# HTMD-PREAMP2.net
KiCad netlist of a schematic drawn in Altium Designer
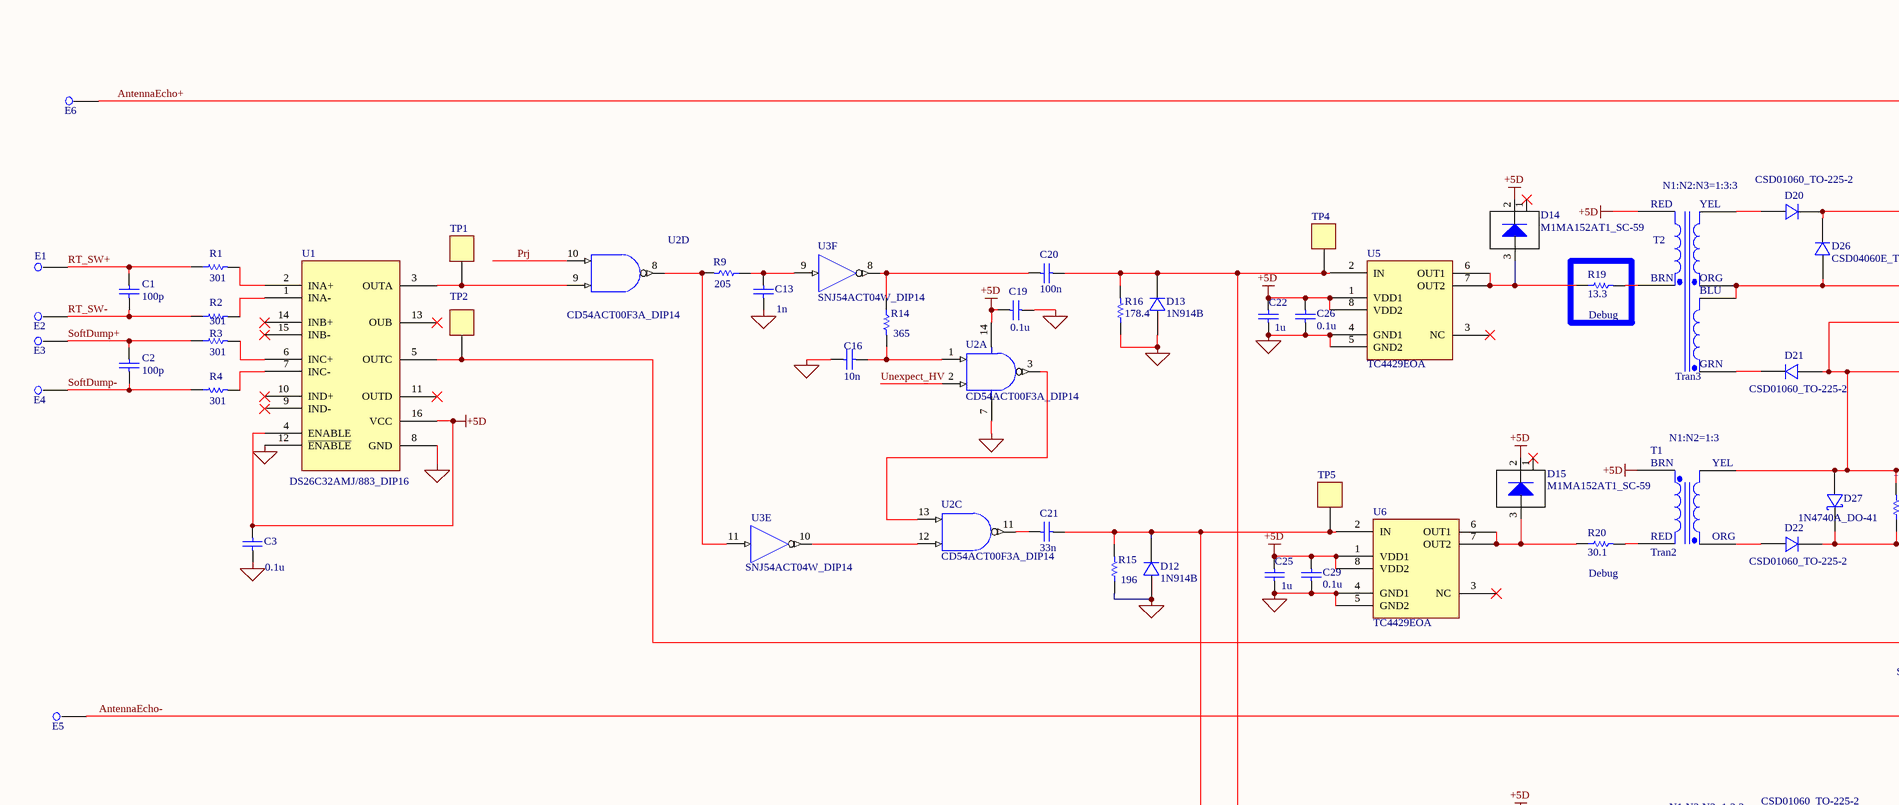
[diagram p0: HTMD-PREAMP2.SCHDOC, top left]
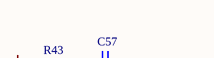
[diagram p1: HTMD-PREAMP2.SCHDOC, top right]
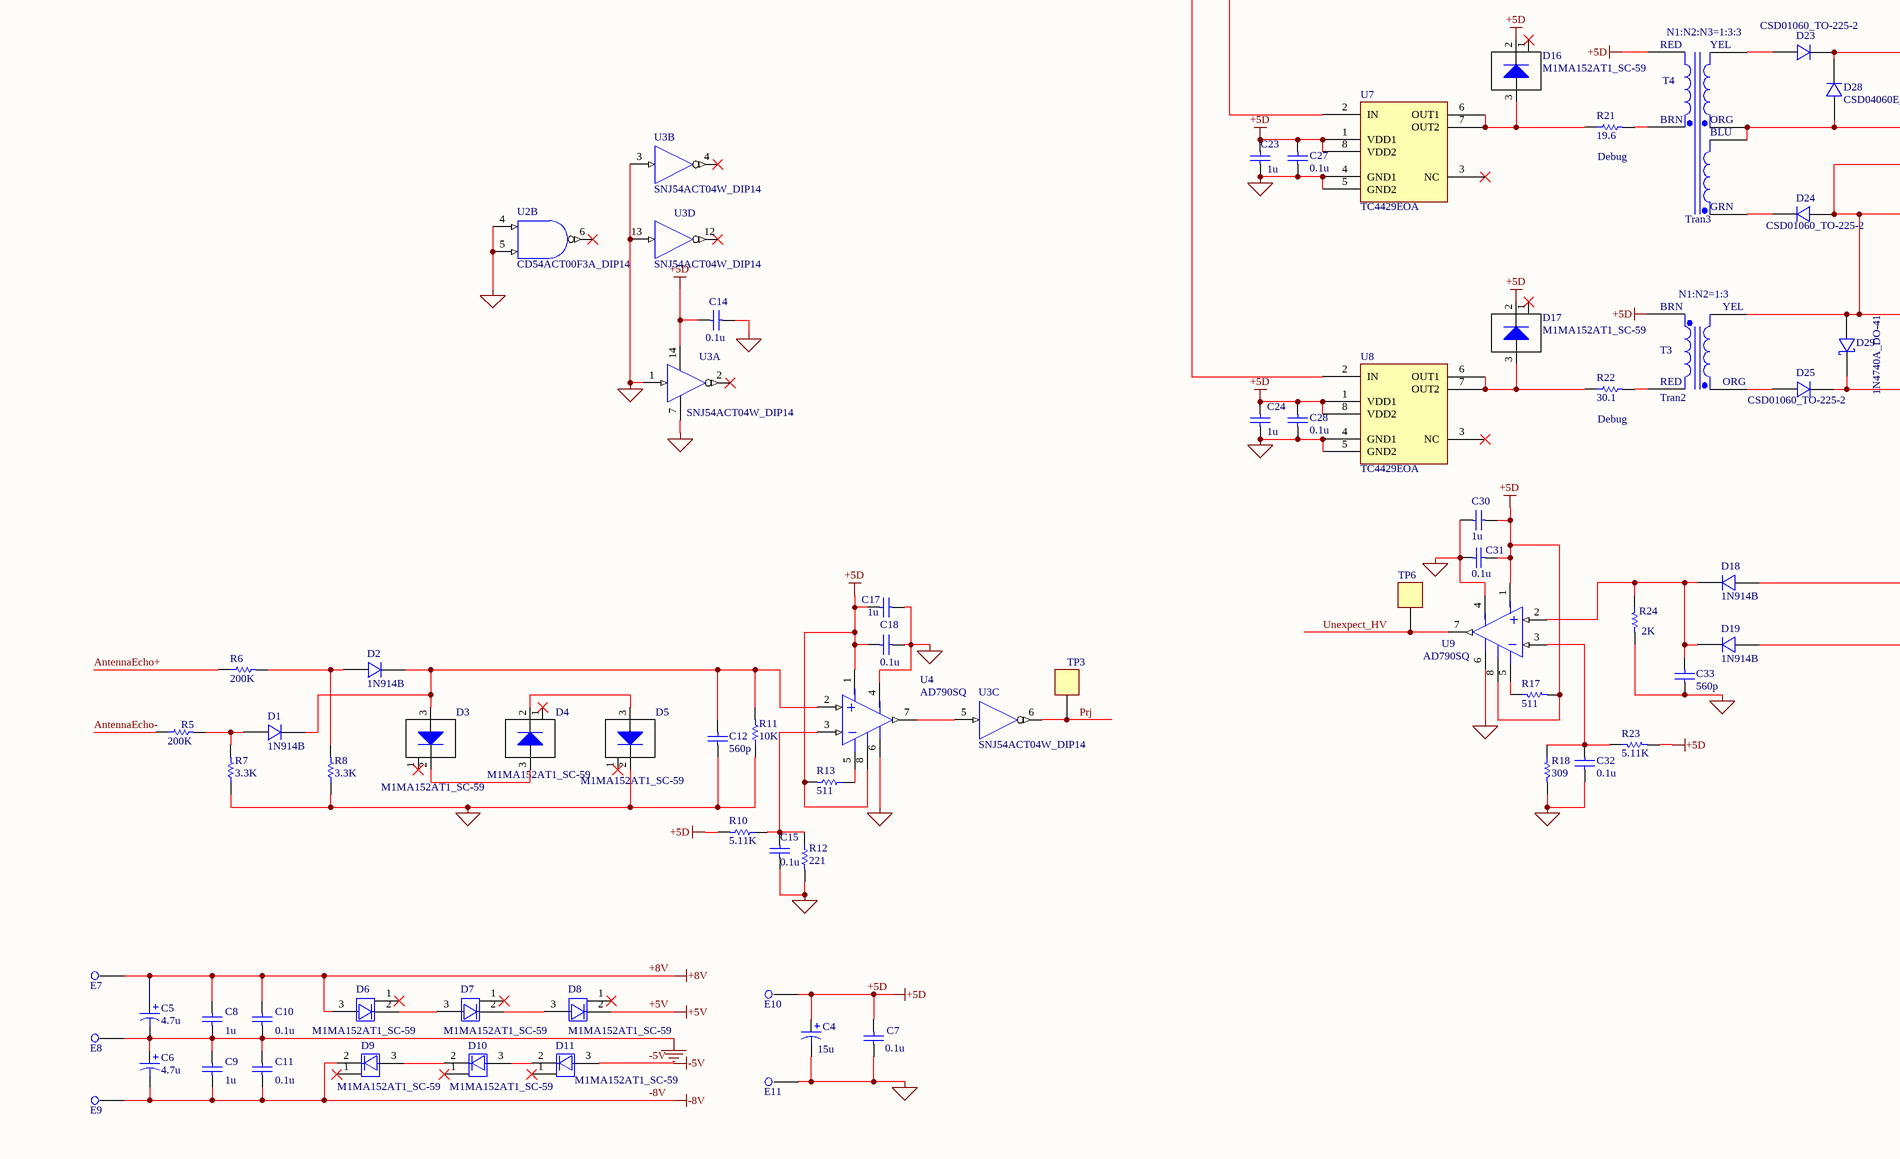
[diagram p2: HTMD-PREAMP2.SCHDOC, bottom left]
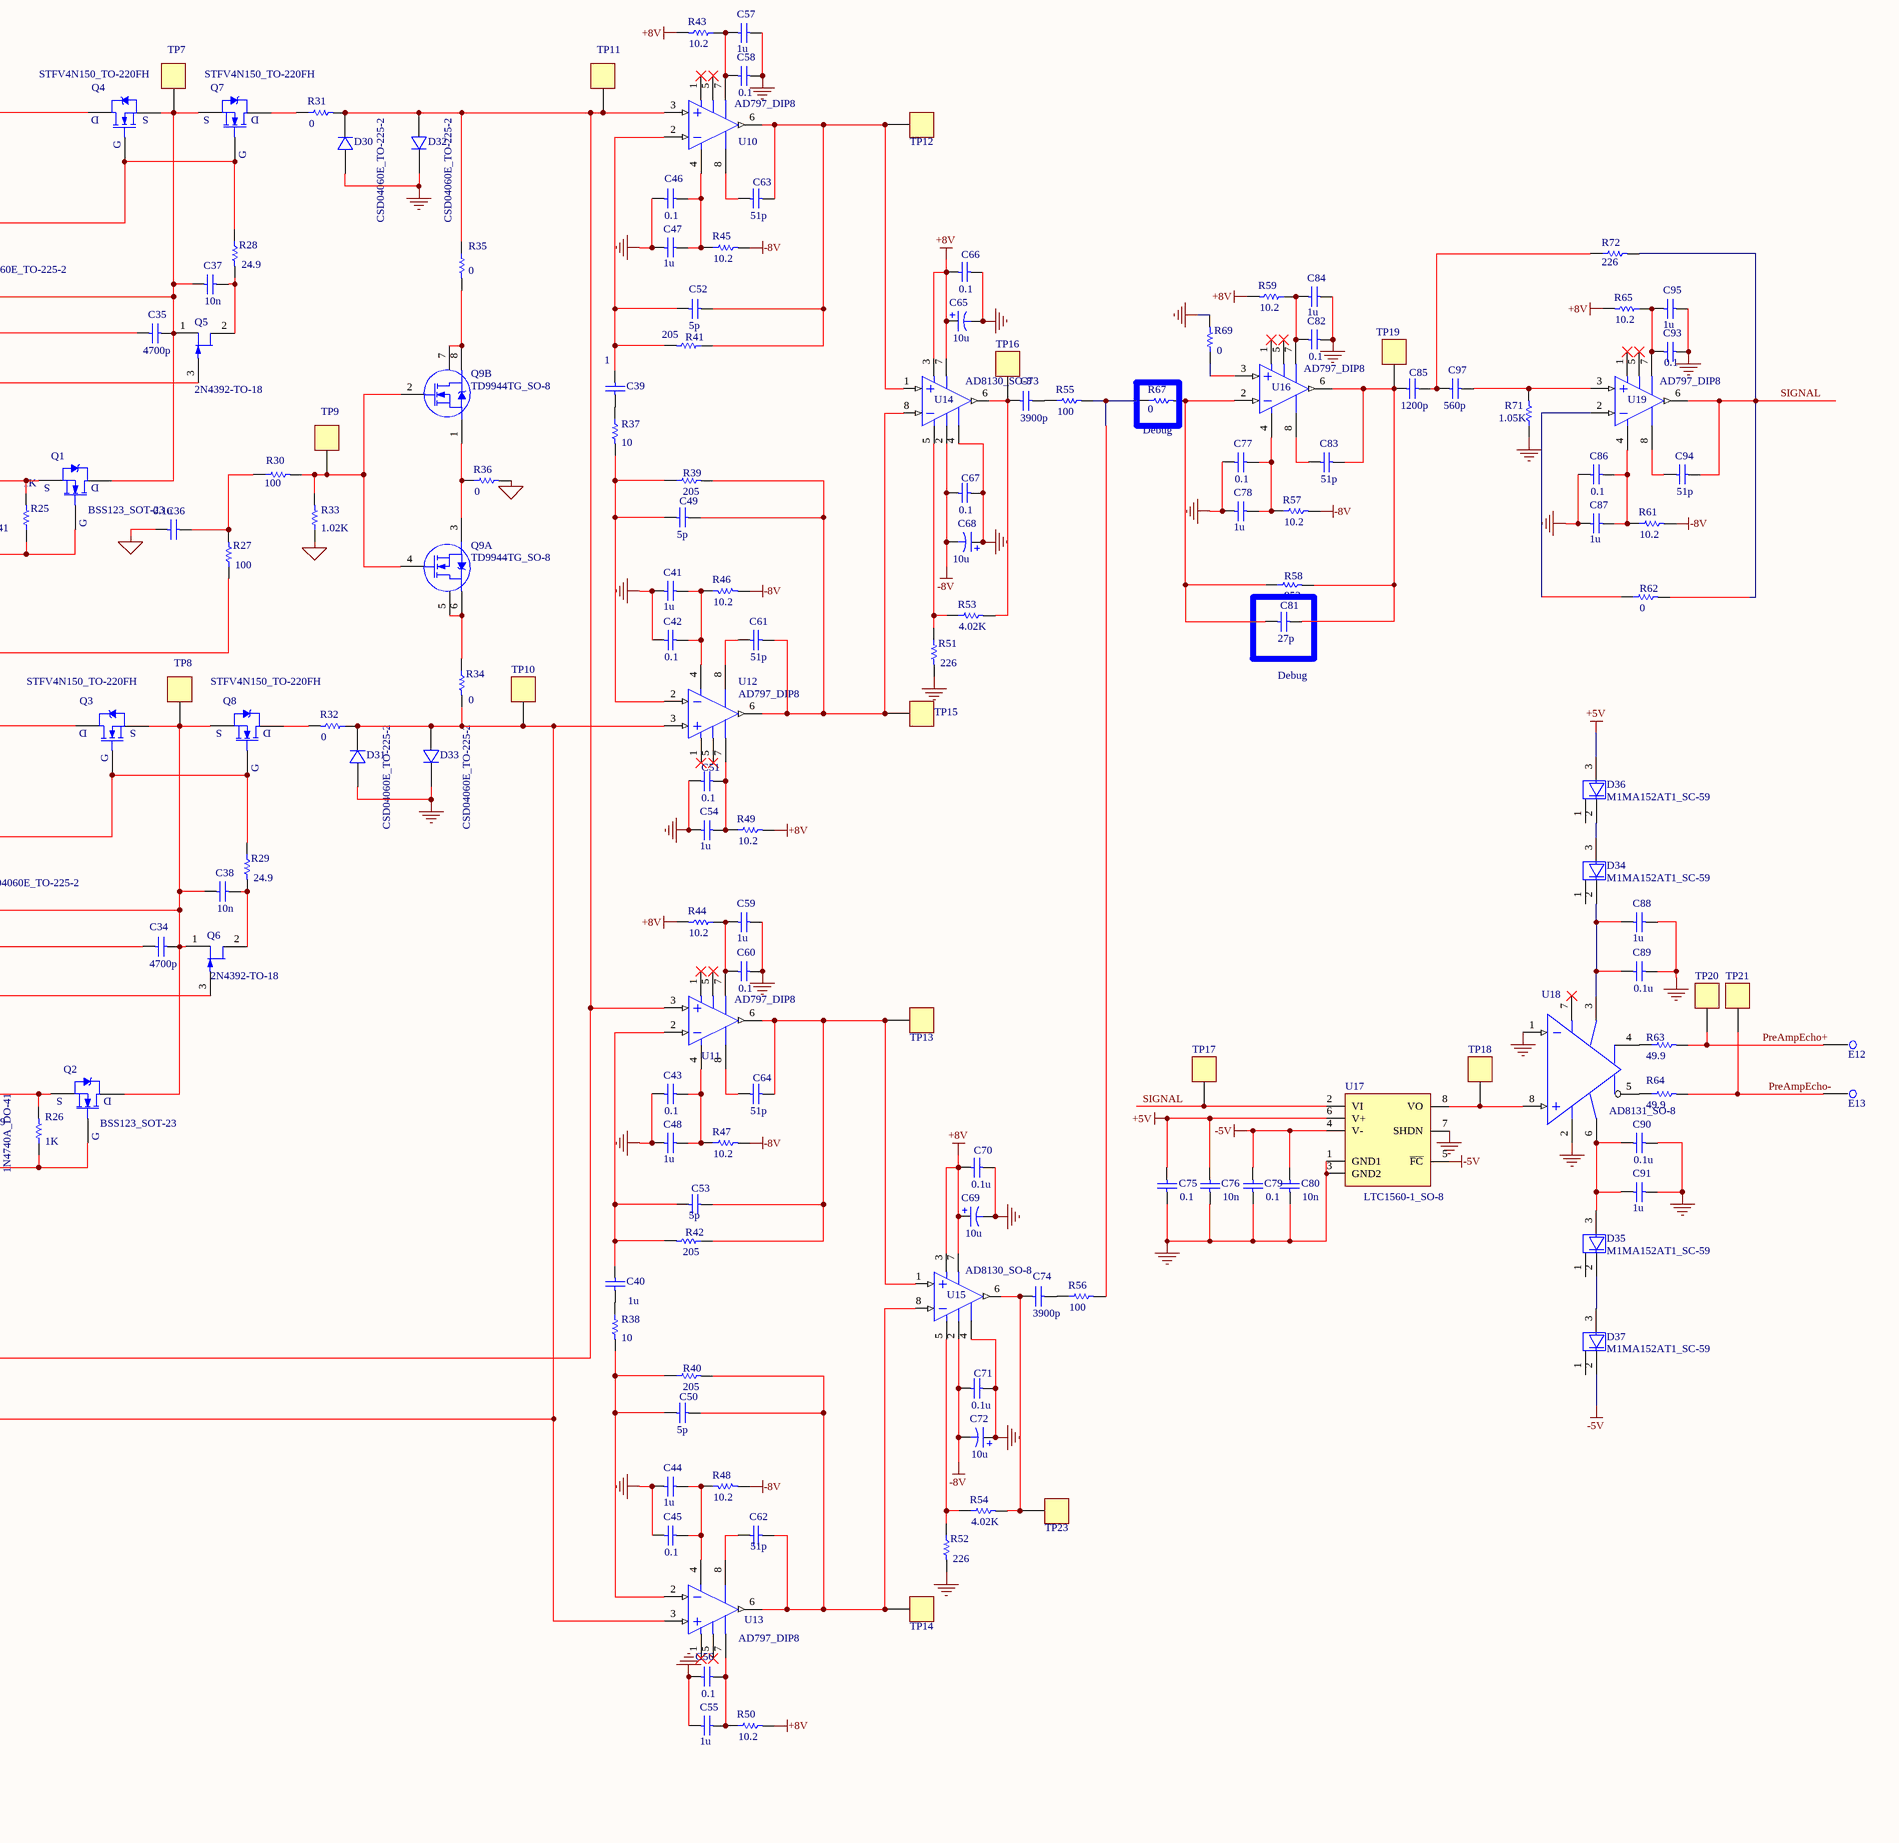
[diagram p3: HTMD-PREAMP2.SCHDOC, bottom right]

(export (version "E")
  (design (tool "Eeschema 10.0.6"))
  (components
    (comp (ref "C1")
      (value "100p")
      (footprint "C0805")
      (description "Capacitor")
      (fields (field (name "PUBLISHER") "Altium Limited"))
      (libsource (lib "*") (part "Cap"))
    )
    (comp (ref "C2")
      (value "100p")
      (footprint "C0805")
      (description "Capacitor")
      (fields (field (name "PUBLISHER") "Altium Limited"))
      (libsource (lib "*") (part "Cap"))
    )
    (comp (ref "C3")
      (value "0.1u")
      (footprint "C0805")
      (description "Capacitor")
      (fields (field (name "PUBLISHER") "Altium Limited"))
      (libsource (lib "*") (part "Cap"))
    )
    (comp (ref "C4")
      (value "15u")
      (footprint "7343")
      (description "Polarized Capacitor (Radial)")
      (fields (field (name "PUBLISHER") "Altium Limited"))
      (libsource (lib "*") (part "Cap Pol1"))
    )
    (comp (ref "C5")
      (value "4.7u")
      (footprint "7343")
      (description "Polarized Capacitor (Radial)")
      (fields (field (name "PUBLISHER") "Altium Limited"))
      (libsource (lib "*") (part "Cap Pol1"))
    )
    (comp (ref "C6")
      (value "4.7u")
      (footprint "7343")
      (description "Polarized Capacitor (Radial)")
      (fields (field (name "PUBLISHER") "Altium Limited"))
      (libsource (lib "*") (part "Cap Pol1"))
    )
    (comp (ref "C7")
      (value "0.1u")
      (footprint "C0805")
      (description "Capacitor")
      (fields (field (name "PUBLISHER") "Altium Limited"))
      (libsource (lib "*") (part "Cap"))
    )
    (comp (ref "C8")
      (value "1u")
      (footprint "C1206")
      (description "Capacitor")
      (fields (field (name "PUBLISHER") "Altium Limited"))
      (libsource (lib "*") (part "Cap"))
    )
    (comp (ref "C9")
      (value "1u")
      (footprint "C1206")
      (description "Capacitor")
      (fields (field (name "PUBLISHER") "Altium Limited"))
      (libsource (lib "*") (part "Cap"))
    )
    (comp (ref "C10")
      (value "0.1u")
      (footprint "C0805")
      (description "Capacitor")
      (fields (field (name "PUBLISHER") "Altium Limited"))
      (libsource (lib "*") (part "Cap"))
    )
    (comp (ref "C11")
      (value "0.1u")
      (footprint "C0805")
      (description "Capacitor")
      (fields (field (name "PUBLISHER") "Altium Limited"))
      (libsource (lib "*") (part "Cap"))
    )
    (comp (ref "C12")
      (value "560p")
      (footprint "C0805")
      (description "Capacitor")
      (fields (field (name "PUBLISHER") "Altium Limited"))
      (libsource (lib "Miscellaneous Devices") (part "Cap"))
    )
    (comp (ref "C13")
      (value "1n")
      (footprint "1206")
      (description "Capacitor")
      (fields (field (name "PUBLISHER") "Altium Limited"))
      (libsource (lib "*") (part "Cap"))
    )
    (comp (ref "C14")
      (value "0.1u")
      (footprint "C0805")
      (description "Capacitor")
      (fields (field (name "PUBLISHER") "Altium Limited"))
      (libsource (lib "*") (part "Cap"))
    )
    (comp (ref "C15")
      (value "0.1u")
      (footprint "C0805")
      (description "Capacitor")
      (fields (field (name "PUBLISHER") "Altium Limited"))
      (libsource (lib "*") (part "Cap"))
    )
    (comp (ref "C16")
      (value "10n")
      (footprint "C0805")
      (description "Capacitor")
      (fields (field (name "PUBLISHER") "Altium Limited"))
      (libsource (lib "*") (part "Cap"))
    )
    (comp (ref "C17")
      (value "1u")
      (footprint "C1206")
      (description "Capacitor")
      (fields (field (name "PUBLISHER") "Altium Limited"))
      (libsource (lib "*") (part "Cap"))
    )
    (comp (ref "C18")
      (value "0.1u")
      (footprint "C0805")
      (description "Capacitor")
      (fields (field (name "PUBLISHER") "Altium Limited"))
      (libsource (lib "*") (part "Cap"))
    )
    (comp (ref "C19")
      (value "0.1u")
      (footprint "C0805")
      (description "Capacitor")
      (fields (field (name "PUBLISHER") "Altium Limited"))
      (libsource (lib "*") (part "Cap"))
    )
    (comp (ref "C20")
      (value "100n")
      (footprint "C0805")
      (description "Capacitor")
      (fields (field (name "PUBLISHER") "Altium Limited"))
      (libsource (lib "*") (part "Cap"))
    )
    (comp (ref "C21")
      (value "33n")
      (footprint "1206")
      (description "Capacitor")
      (fields (field (name "PUBLISHER") "Altium Limited"))
      (libsource (lib "*") (part "Cap"))
    )
    (comp (ref "C22")
      (value "1u")
      (footprint "C1206")
      (description "Capacitor")
      (fields (field (name "PUBLISHER") "Altium Limited"))
      (libsource (lib "*") (part "Cap"))
    )
    (comp (ref "C23")
      (value "1u")
      (footprint "C1206")
      (description "Capacitor")
      (fields (field (name "PUBLISHER") "Altium Limited"))
      (libsource (lib "*") (part "Cap"))
    )
    (comp (ref "C24")
      (value "1u")
      (footprint "C1206")
      (description "Capacitor")
      (fields (field (name "PUBLISHER") "Altium Limited"))
      (libsource (lib "*") (part "Cap"))
    )
    (comp (ref "C25")
      (value "1u")
      (footprint "C1206")
      (description "Capacitor")
      (fields (field (name "PUBLISHER") "Altium Limited"))
      (libsource (lib "*") (part "Cap"))
    )
    (comp (ref "C26")
      (value "0.1u")
      (footprint "C0805")
      (description "Capacitor")
      (fields (field (name "PUBLISHER") "Altium Limited"))
      (libsource (lib "*") (part "Cap"))
    )
    (comp (ref "C27")
      (value "0.1u")
      (footprint "C0805")
      (description "Capacitor")
      (fields (field (name "PUBLISHER") "Altium Limited"))
      (libsource (lib "*") (part "Cap"))
    )
    (comp (ref "C28")
      (value "0.1u")
      (footprint "C0805")
      (description "Capacitor")
      (fields (field (name "PUBLISHER") "Altium Limited"))
      (libsource (lib "*") (part "Cap"))
    )
    (comp (ref "C29")
      (value "0.1u")
      (footprint "C0805")
      (description "Capacitor")
      (fields (field (name "PUBLISHER") "Altium Limited"))
      (libsource (lib "*") (part "Cap"))
    )
    (comp (ref "C30")
      (value "1u")
      (footprint "C1206")
      (description "Capacitor")
      (fields (field (name "PUBLISHER") "Altium Limited"))
      (libsource (lib "*") (part "Cap"))
    )
    (comp (ref "C31")
      (value "0.1u")
      (footprint "C0805")
      (description "Capacitor")
      (fields (field (name "PUBLISHER") "Altium Limited"))
      (libsource (lib "*") (part "Cap"))
    )
    (comp (ref "C32")
      (value "0.1u")
      (footprint "C0805")
      (description "Capacitor")
      (fields (field (name "PUBLISHER") "Altium Limited"))
      (libsource (lib "*") (part "Cap"))
    )
    (comp (ref "C33")
      (value "560p")
      (footprint "C0805")
      (description "Capacitor")
      (fields (field (name "PUBLISHER") "Altium Limited"))
      (libsource (lib "*") (part "Cap"))
    )
    (comp (ref "C34")
      (value "4700p")
      (footprint "C0805")
      (description "Capacitor")
      (fields (field (name "PUBLISHER") "Altium Limited"))
      (libsource (lib "*") (part "Cap"))
    )
    (comp (ref "C35")
      (value "4700p")
      (footprint "C0805")
      (description "Capacitor")
      (fields (field (name "PUBLISHER") "Altium Limited"))
      (libsource (lib "*") (part "Cap"))
    )
    (comp (ref "C36")
      (value "0.1u")
      (footprint "C0805")
      (description "Capacitor")
      (fields (field (name "PUBLISHER") "Altium Limited"))
      (libsource (lib "*") (part "Cap"))
    )
    (comp (ref "C37")
      (value "10n")
      (footprint "1206")
      (description "Capacitor")
      (fields (field (name "PUBLISHER") "Altium Limited"))
      (libsource (lib "*") (part "Cap"))
    )
    (comp (ref "C38")
      (value "10n")
      (footprint "1206")
      (description "Capacitor")
      (fields (field (name "PUBLISHER") "Altium Limited"))
      (libsource (lib "*") (part "Cap"))
    )
    (comp (ref "C39")
      (value "1")
      (footprint "1206")
      (description "Capacitor")
      (fields (field (name "PUBLISHER") "Altium Limited"))
      (libsource (lib "*") (part "Cap"))
    )
    (comp (ref "C40")
      (value "1u")
      (footprint "1206")
      (description "Capacitor")
      (fields (field (name "PUBLISHER") "Altium Limited"))
      (libsource (lib "*") (part "Cap"))
    )
    (comp (ref "C41")
      (value "1u")
      (footprint "C1206")
      (description "Capacitor")
      (fields (field (name "PUBLISHER") "Altium Limited"))
      (libsource (lib "*") (part "Cap"))
    )
    (comp (ref "C42")
      (value "0.1")
      (footprint "C0805")
      (description "Capacitor")
      (fields (field (name "PUBLISHER") "Altium Limited"))
      (libsource (lib "*") (part "Cap"))
    )
    (comp (ref "C43")
      (value "0.1")
      (footprint "C0805")
      (description "Capacitor")
      (fields (field (name "PUBLISHER") "Altium Limited"))
      (libsource (lib "*") (part "Cap"))
    )
    (comp (ref "C44")
      (value "1u")
      (footprint "C1206")
      (description "Capacitor")
      (fields (field (name "PUBLISHER") "Altium Limited"))
      (libsource (lib "*") (part "Cap"))
    )
    (comp (ref "C45")
      (value "0.1")
      (footprint "C0805")
      (description "Capacitor")
      (fields (field (name "PUBLISHER") "Altium Limited"))
      (libsource (lib "*") (part "Cap"))
    )
    (comp (ref "C46")
      (value "0.1")
      (footprint "C0805")
      (description "Capacitor")
      (fields (field (name "PUBLISHER") "Altium Limited"))
      (libsource (lib "*") (part "Cap"))
    )
    (comp (ref "C47")
      (value "1u")
      (footprint "C1206")
      (description "Capacitor")
      (fields (field (name "PUBLISHER") "Altium Limited"))
      (libsource (lib "*") (part "Cap"))
    )
    (comp (ref "C48")
      (value "1u")
      (footprint "C1206")
      (description "Capacitor")
      (fields (field (name "PUBLISHER") "Altium Limited"))
      (libsource (lib "*") (part "Cap"))
    )
    (comp (ref "C49")
      (value "5p")
      (footprint "C0805")
      (description "Capacitor")
      (fields (field (name "PUBLISHER") "Altium Limited"))
      (libsource (lib "*") (part "Cap"))
    )
    (comp (ref "C50")
      (value "5p")
      (footprint "C0805")
      (description "Capacitor")
      (fields (field (name "PUBLISHER") "Altium Limited"))
      (libsource (lib "*") (part "Cap"))
    )
    (comp (ref "C51")
      (value "0.1")
      (footprint "C0805")
      (description "Capacitor")
      (fields (field (name "PUBLISHER") "Altium Limited"))
      (libsource (lib "*") (part "Cap"))
    )
    (comp (ref "C52")
      (value "5p")
      (footprint "C0805")
      (description "Capacitor")
      (fields (field (name "PUBLISHER") "Altium Limited"))
      (libsource (lib "*") (part "Cap"))
    )
    (comp (ref "C53")
      (value "5p")
      (footprint "C0805")
      (description "Capacitor")
      (fields (field (name "PUBLISHER") "Altium Limited"))
      (libsource (lib "*") (part "Cap"))
    )
    (comp (ref "C54")
      (value "1u")
      (footprint "C1206")
      (description "Capacitor")
      (fields (field (name "PUBLISHER") "Altium Limited"))
      (libsource (lib "*") (part "Cap"))
    )
    (comp (ref "C55")
      (value "1u")
      (footprint "C1206")
      (description "Capacitor")
      (fields (field (name "PUBLISHER") "Altium Limited"))
      (libsource (lib "*") (part "Cap"))
    )
    (comp (ref "C56")
      (value "0.1")
      (footprint "C0805")
      (description "Capacitor")
      (fields (field (name "PUBLISHER") "Altium Limited"))
      (libsource (lib "*") (part "Cap"))
    )
    (comp (ref "C57")
      (value "1u")
      (footprint "C1206")
      (description "Capacitor")
      (fields (field (name "PUBLISHER") "Altium Limited"))
      (libsource (lib "*") (part "Cap"))
    )
    (comp (ref "C58")
      (value "0.1")
      (footprint "C0805")
      (description "Capacitor")
      (fields (field (name "PUBLISHER") "Altium Limited"))
      (libsource (lib "*") (part "Cap"))
    )
    (comp (ref "C59")
      (value "1u")
      (footprint "C1206")
      (description "Capacitor")
      (fields (field (name "PUBLISHER") "Altium Limited"))
      (libsource (lib "*") (part "Cap"))
    )
    (comp (ref "C60")
      (value "0.1")
      (footprint "C0805")
      (description "Capacitor")
      (fields (field (name "PUBLISHER") "Altium Limited"))
      (libsource (lib "*") (part "Cap"))
    )
    (comp (ref "C61")
      (value "51p")
      (footprint "C0805")
      (description "Capacitor")
      (fields (field (name "PUBLISHER") "Altium Limited"))
      (libsource (lib "*") (part "Cap"))
    )
    (comp (ref "C62")
      (value "51p")
      (footprint "C0805")
      (description "Capacitor")
      (fields (field (name "PUBLISHER") "Altium Limited"))
      (libsource (lib "*") (part "Cap"))
    )
    (comp (ref "C63")
      (value "51p")
      (footprint "C0805")
      (description "Capacitor")
      (fields (field (name "PUBLISHER") "Altium Limited"))
      (libsource (lib "*") (part "Cap"))
    )
    (comp (ref "C64")
      (value "51p")
      (footprint "C0805")
      (description "Capacitor")
      (fields (field (name "PUBLISHER") "Altium Limited"))
      (libsource (lib "*") (part "Cap"))
    )
    (comp (ref "C65")
      (value "10u")
      (footprint "7343")
      (description "Polarized Capacitor (Surface Mount)")
      (fields (field (name "PUBLISHER") "Altium Limited"))
      (libsource (lib "Miscellaneous Devices") (part "Cap Pol3"))
    )
    (comp (ref "C66")
      (value "0.1")
      (footprint "C0805")
      (description "Capacitor")
      (fields (field (name "PUBLISHER") "Altium Limited"))
      (libsource (lib "*") (part "Cap"))
    )
    (comp (ref "C67")
      (value "0.1")
      (footprint "C0805")
      (description "Capacitor")
      (fields (field (name "PUBLISHER") "Altium Limited"))
      (libsource (lib "*") (part "Cap"))
    )
    (comp (ref "C68")
      (value "10u")
      (footprint "7343")
      (description "Polarized Capacitor (Surface Mount)")
      (fields (field (name "PUBLISHER") "Altium Limited"))
      (libsource (lib "Miscellaneous Devices") (part "Cap Pol3"))
    )
    (comp (ref "C69")
      (value "10u")
      (footprint "7343")
      (description "Polarized Capacitor (Surface Mount)")
      (fields (field (name "PUBLISHER") "Altium Limited"))
      (libsource (lib "Miscellaneous Devices") (part "Cap Pol3"))
    )
    (comp (ref "C70")
      (value "0.1u")
      (footprint "C0805")
      (description "Capacitor")
      (fields (field (name "PUBLISHER") "Altium Limited"))
      (libsource (lib "*") (part "Cap"))
    )
    (comp (ref "C71")
      (value "0.1u")
      (footprint "C0805")
      (description "Capacitor")
      (fields (field (name "PUBLISHER") "Altium Limited"))
      (libsource (lib "*") (part "Cap"))
    )
    (comp (ref "C72")
      (value "10u")
      (footprint "7343")
      (description "Polarized Capacitor (Surface Mount)")
      (fields (field (name "PUBLISHER") "Altium Limited"))
      (libsource (lib "Miscellaneous Devices") (part "Cap Pol3"))
    )
    (comp (ref "C73")
      (value "3900p")
      (footprint "1206")
      (description "Capacitor")
      (fields (field (name "PUBLISHER") "Altium Limited"))
      (libsource (lib "*") (part "Cap"))
    )
    (comp (ref "C74")
      (value "3900p")
      (footprint "1206")
      (description "Capacitor")
      (fields (field (name "PUBLISHER") "Altium Limited"))
      (libsource (lib "*") (part "Cap"))
    )
    (comp (ref "C75")
      (value "0.1")
      (footprint "C0805")
      (description "Capacitor")
      (fields (field (name "PUBLISHER") "Altium Limited"))
      (libsource (lib "*") (part "Cap"))
    )
    (comp (ref "C76")
      (value "10n")
      (footprint "C0805")
      (description "Capacitor")
      (fields (field (name "PUBLISHER") "Altium Limited"))
      (libsource (lib "*") (part "Cap"))
    )
    (comp (ref "C77")
      (value "0.1")
      (footprint "C0805")
      (description "Capacitor")
      (fields (field (name "PUBLISHER") "Altium Limited"))
      (libsource (lib "*") (part "Cap"))
    )
    (comp (ref "C78")
      (value "1u")
      (footprint "C1206")
      (description "Capacitor")
      (fields (field (name "PUBLISHER") "Altium Limited"))
      (libsource (lib "*") (part "Cap"))
    )
    (comp (ref "C79")
      (value "0.1")
      (footprint "C0805")
      (description "Capacitor")
      (fields (field (name "PUBLISHER") "Altium Limited"))
      (libsource (lib "*") (part "Cap"))
    )
    (comp (ref "C80")
      (value "10n")
      (footprint "C0805")
      (description "Capacitor")
      (fields (field (name "PUBLISHER") "Altium Limited"))
      (libsource (lib "*") (part "Cap"))
    )
    (comp (ref "C81")
      (value "27p")
      (footprint "C0805")
      (description "Capacitor")
      (fields (field (name "PUBLISHER") "Altium Limited"))
      (libsource (lib "*") (part "Cap"))
    )
    (comp (ref "C82")
      (value "0.1")
      (footprint "C0805")
      (description "Capacitor")
      (fields (field (name "PUBLISHER") "Altium Limited"))
      (libsource (lib "*") (part "Cap"))
    )
    (comp (ref "C83")
      (value "51p")
      (footprint "C0805")
      (description "Capacitor")
      (fields (field (name "PUBLISHER") "Altium Limited"))
      (libsource (lib "*") (part "Cap"))
    )
    (comp (ref "C84")
      (value "1u")
      (footprint "C1206")
      (description "Capacitor")
      (fields (field (name "PUBLISHER") "Altium Limited"))
      (libsource (lib "*") (part "Cap"))
    )
    (comp (ref "C85")
      (value "1200p")
      (footprint "C0805")
      (description "Capacitor")
      (fields (field (name "PUBLISHER") "Altium Limited"))
      (libsource (lib "*") (part "Cap"))
    )
    (comp (ref "C86")
      (value "0.1")
      (footprint "C0805")
      (description "Capacitor")
      (fields (field (name "PUBLISHER") "Altium Limited"))
      (libsource (lib "*") (part "Cap"))
    )
    (comp (ref "C87")
      (value "1u")
      (footprint "C1206")
      (description "Capacitor")
      (fields (field (name "PUBLISHER") "Altium Limited"))
      (libsource (lib "*") (part "Cap"))
    )
    (comp (ref "C88")
      (value "1u")
      (footprint "C1206")
      (description "Capacitor")
      (fields (field (name "PUBLISHER") "Altium Limited"))
      (libsource (lib "*") (part "Cap"))
    )
    (comp (ref "C89")
      (value "0.1u")
      (footprint "C0805")
      (description "Capacitor")
      (fields (field (name "PUBLISHER") "Altium Limited"))
      (libsource (lib "*") (part "Cap"))
    )
    (comp (ref "C90")
      (value "0.1u")
      (footprint "C0805")
      (description "Capacitor")
      (fields (field (name "PUBLISHER") "Altium Limited"))
      (libsource (lib "*") (part "Cap"))
    )
    (comp (ref "C91")
      (value "1u")
      (footprint "C1206")
      (description "Capacitor")
      (fields (field (name "PUBLISHER") "Altium Limited"))
      (libsource (lib "*") (part "Cap"))
    )
    (comp (ref "C93")
      (value "0.1")
      (footprint "C0805")
      (description "Capacitor")
      (fields (field (name "PUBLISHER") "Altium Limited"))
      (libsource (lib "*") (part "Cap"))
    )
    (comp (ref "C94")
      (value "51p")
      (footprint "C0805")
      (description "Capacitor")
      (fields (field (name "PUBLISHER") "Altium Limited"))
      (libsource (lib "*") (part "Cap"))
    )
    (comp (ref "C95")
      (value "1u")
      (footprint "C1206")
      (description "Capacitor")
      (fields (field (name "PUBLISHER") "Altium Limited"))
      (libsource (lib "*") (part "Cap"))
    )
    (comp (ref "C97")
      (value "560p")
      (footprint "C0805")
      (description "Capacitor")
      (fields (field (name "PUBLISHER") "Altium Limited"))
      (libsource (lib "Miscellaneous Devices") (part "Cap"))
    )
    (comp (ref "D1") (value "1N914B") (footprint "DO-35") (libsource (lib "*") (part "1N914B")))
    (comp (ref "D2") (value "1N914B") (footprint "DO-35") (libsource (lib "*") (part "1N914B")))
    (comp (ref "D3")
      (value "M1MA152AT1_SC-59")
      (footprint "SC-59")
      (description "single silicon switching diodes")
      (fields (field (name "PUBLISHER") "Altium Limited"))
      (libsource (lib "") (part "M1MA152AT1_1"))
    )
    (comp (ref "D4")
      (value "M1MA152AT1_SC-59")
      (footprint "SC-59")
      (description "single silicon switching diodes")
      (fields (field (name "PUBLISHER") "Altium Limited"))
      (libsource (lib "") (part "M1MA152AT1_1"))
    )
    (comp (ref "D5")
      (value "M1MA152AT1_SC-59")
      (footprint "SC-59")
      (description "single silicon switching diodes")
      (fields (field (name "PUBLISHER") "Altium Limited"))
      (libsource (lib "") (part "M1MA152AT1_1"))
    )
    (comp (ref "D6") (value "M1MA152AT1_SC-59") (footprint "SC-59") (libsource (lib "*") (part "M1MA152AT1")))
    (comp (ref "D7") (value "M1MA152AT1_SC-59") (footprint "SC-59") (libsource (lib "*") (part "M1MA152AT1")))
    (comp (ref "D8") (value "M1MA152AT1_SC-59") (footprint "SC-59") (libsource (lib "*") (part "M1MA152AT1")))
    (comp (ref "D9") (value "M1MA152AT1_SC-59") (footprint "SC-59") (libsource (lib "*") (part "M1MA152AT1")))
    (comp (ref "D10")
      (value "M1MA152AT1_SC-59")
      (footprint "SC-59")
      (libsource (lib "*") (part "M1MA152AT1"))
    )
    (comp (ref "D11")
      (value "M1MA152AT1_SC-59")
      (footprint "SC-59")
      (libsource (lib "*") (part "M1MA152AT1"))
    )
    (comp (ref "D12") (value "1N914B") (footprint "DO-35") (libsource (lib "*") (part "1N914B")))
    (comp (ref "D13") (value "1N914B") (footprint "DO-35") (libsource (lib "*") (part "1N914B")))
    (comp (ref "D14")
      (value "M1MA152AT1_SC-59")
      (footprint "SC-59")
      (description "single silicon switching diodes")
      (fields (field (name "PUBLISHER") "Altium Limited"))
      (libsource (lib "*") (part "M1MA152AT1_1"))
    )
    (comp (ref "D15")
      (value "M1MA152AT1_SC-59")
      (footprint "SC-59")
      (description "single silicon switching diodes")
      (fields (field (name "PUBLISHER") "Altium Limited"))
      (libsource (lib "*") (part "M1MA152AT1_1"))
    )
    (comp (ref "D16")
      (value "M1MA152AT1_SC-59")
      (footprint "SC-59")
      (description "single silicon switching diodes")
      (fields (field (name "PUBLISHER") "Altium Limited"))
      (libsource (lib "*") (part "M1MA152AT1_1"))
    )
    (comp (ref "D17")
      (value "M1MA152AT1_SC-59")
      (footprint "SC-59")
      (description "single silicon switching diodes")
      (fields (field (name "PUBLISHER") "Altium Limited"))
      (libsource (lib "*") (part "M1MA152AT1_1"))
    )
    (comp (ref "D18") (value "1N914B") (footprint "DO-35") (libsource (lib "*") (part "1N914B")))
    (comp (ref "D19") (value "1N914B") (footprint "DO-35") (libsource (lib "*") (part "1N914B")))
    (comp (ref "D20")
      (value "CSD01060_TO-225-2")
      (footprint "TO-225-2")
      (description "CSD01060")
      (libsource (lib "*") (part "CSD01060"))
    )
    (comp (ref "D21")
      (value "CSD01060_TO-225-2")
      (footprint "TO-225-2")
      (description "CSD01060")
      (libsource (lib "*") (part "CSD01060"))
    )
    (comp (ref "D22")
      (value "CSD01060_TO-225-2")
      (footprint "TO-225-2")
      (description "CSD01060")
      (libsource (lib "*") (part "CSD01060"))
    )
    (comp (ref "D23")
      (value "CSD01060_TO-225-2")
      (footprint "TO-225-2")
      (description "CSD01060")
      (libsource (lib "*") (part "CSD01060"))
    )
    (comp (ref "D24")
      (value "CSD01060_TO-225-2")
      (footprint "TO-225-2")
      (description "CSD01060")
      (libsource (lib "*") (part "CSD01060"))
    )
    (comp (ref "D25")
      (value "CSD01060_TO-225-2")
      (footprint "TO-225-2")
      (description "CSD01060")
      (libsource (lib "*") (part "CSD01060"))
    )
    (comp (ref "D26")
      (value "CSD04060E_TO-225-2")
      (footprint "TO-225-2")
      (description "CSD04060E")
      (libsource (lib "*") (part "CSD04060E"))
    )
    (comp (ref "D27")
      (value "1N4740A_DO-41")
      (footprint "DO-41")
      (description "Schottky Rectifier")
      (libsource (lib "*") (part "1N4740A"))
    )
    (comp (ref "D28")
      (value "CSD04060E_TO-225-2")
      (footprint "TO-225-2")
      (description "CSD04060E")
      (libsource (lib "*") (part "CSD04060E"))
    )
    (comp (ref "D29")
      (value "1N4740A_DO-41")
      (footprint "DO-41")
      (description "Schottky Rectifier")
      (libsource (lib "*") (part "1N4740A"))
    )
    (comp (ref "D30")
      (value "CSD04060E_TO-225-2")
      (footprint "TO-225-2")
      (description "CSD04060E")
      (libsource (lib "*") (part "CSD04060E"))
    )
    (comp (ref "D31")
      (value "CSD04060E_TO-225-2")
      (footprint "TO-225-2")
      (description "CSD04060E")
      (libsource (lib "*") (part "CSD04060E"))
    )
    (comp (ref "D32")
      (value "CSD04060E_TO-225-2")
      (footprint "TO-225-2")
      (description "CSD04060E")
      (libsource (lib "*") (part "CSD04060E"))
    )
    (comp (ref "D33")
      (value "CSD04060E_TO-225-2")
      (footprint "TO-225-2")
      (description "CSD04060E")
      (libsource (lib "*") (part "CSD04060E"))
    )
    (comp (ref "D34")
      (value "M1MA152AT1_SC-59")
      (footprint "SC-59")
      (libsource (lib "*") (part "M1MA152AT1"))
    )
    (comp (ref "D35")
      (value "M1MA152AT1_SC-59")
      (footprint "SC-59")
      (libsource (lib "*") (part "M1MA152AT1"))
    )
    (comp (ref "D36")
      (value "M1MA152AT1_SC-59")
      (footprint "SC-59")
      (libsource (lib "*") (part "M1MA152AT1"))
    )
    (comp (ref "D37")
      (value "M1MA152AT1_SC-59")
      (footprint "SC-59")
      (libsource (lib "*") (part "M1MA152AT1"))
    )
    (comp (ref "E1") (value "InOut") (footprint "TermSignal") (libsource (lib "PreAmp") (part "InOut")))
    (comp (ref "E2") (value "InOut") (footprint "TermSignal") (libsource (lib "*") (part "InOut")))
    (comp (ref "E3") (value "InOut") (footprint "TermSignal") (libsource (lib "*") (part "InOut")))
    (comp (ref "E4") (value "InOut") (footprint "TermSignal") (libsource (lib "*") (part "InOut")))
    (comp (ref "E5") (value "InOut") (footprint "TermSignal") (libsource (lib "*") (part "InOut")))
    (comp (ref "E6") (value "InOut") (footprint "TermSignal") (libsource (lib "*") (part "InOut")))
    (comp (ref "E7") (value "InOut") (footprint "TermPower") (libsource (lib "*") (part "InOut")))
    (comp (ref "E8") (value "InOut") (footprint "TermPower") (libsource (lib "*") (part "InOut")))
    (comp (ref "E9") (value "InOut") (footprint "TermPower") (libsource (lib "*") (part "InOut")))
    (comp (ref "E10") (value "InOut") (footprint "TermPower") (libsource (lib "*") (part "InOut")))
    (comp (ref "E11") (value "InOut") (footprint "TermPower") (libsource (lib "*") (part "InOut")))
    (comp (ref "E12") (value "InOut") (footprint "TermSignal") (libsource (lib "*") (part "InOut")))
    (comp (ref "E13") (value "InOut") (footprint "TermSignal") (libsource (lib "*") (part "InOut")))
    (comp (ref "Q1")
      (value "BSS123_SOT-23")
      (footprint "SOT-23")
      (description "BSS123")
      (libsource (lib "*") (part "BSS123"))
    )
    (comp (ref "Q2")
      (value "BSS123_SOT-23")
      (footprint "SOT-23")
      (description "BSS123")
      (libsource (lib "*") (part "BSS123"))
    )
    (comp (ref "Q3")
      (value "STFV4N150_TO-220FH")
      (footprint "TO-220FH")
      (libsource (lib "*") (part "STFV4N150"))
    )
    (comp (ref "Q4")
      (value "STFV4N150_TO-220FH")
      (footprint "TO-220FH")
      (libsource (lib "*") (part "STFV4N150"))
    )
    (comp (ref "Q5") (value "2N4392-TO-18") (footprint "TO-18") (libsource (lib "*") (part "MPF4392")))
    (comp (ref "Q6") (value "2N4392-TO-18") (footprint "TO-18") (libsource (lib "*") (part "MPF4392")))
    (comp (ref "Q7")
      (value "STFV4N150_TO-220FH")
      (footprint "TO-220FH")
      (libsource (lib "*") (part "STFV4N150"))
    )
    (comp (ref "Q8")
      (value "STFV4N150_TO-220FH")
      (footprint "TO-220FH")
      (libsource (lib "*") (part "STFV4N150"))
    )
    (comp (ref "Q9") (value "TD9944TG_SO-8") (footprint "SO-8") (libsource (lib "*") (part "TD9944")))
    (comp (ref "R1")
      (value "301")
      (footprint "R0805")
      (description "Resistor")
      (fields (field (name "PUBLISHER") "Altium Limited"))
      (libsource (lib "*") (part "Res1"))
    )
    (comp (ref "R2")
      (value "301")
      (footprint "R0805")
      (description "Resistor")
      (fields (field (name "PUBLISHER") "Altium Limited"))
      (libsource (lib "*") (part "Res1"))
    )
    (comp (ref "R3")
      (value "301")
      (footprint "R0805")
      (description "Resistor")
      (fields (field (name "PUBLISHER") "Altium Limited"))
      (libsource (lib "*") (part "Res1"))
    )
    (comp (ref "R4")
      (value "301")
      (footprint "R0805")
      (description "Resistor")
      (fields (field (name "PUBLISHER") "Altium Limited"))
      (libsource (lib "*") (part "Res1"))
    )
    (comp (ref "R5")
      (value "200K")
      (footprint "MG680")
      (description "Resistor")
      (fields (field (name "PUBLISHER") "Altium Limited"))
      (libsource (lib "*") (part "Res1"))
    )
    (comp (ref "R6")
      (value "200K")
      (footprint "MG680")
      (description "Resistor")
      (fields (field (name "PUBLISHER") "Altium Limited"))
      (libsource (lib "*") (part "Res1"))
    )
    (comp (ref "R7")
      (value "3.3K")
      (footprint "2010")
      (description "Resistor")
      (fields (field (name "PUBLISHER") "Altium Limited"))
      (libsource (lib "*") (part "Res1"))
    )
    (comp (ref "R8")
      (value "3.3K")
      (footprint "2010")
      (description "Resistor")
      (fields (field (name "PUBLISHER") "Altium Limited"))
      (libsource (lib "*") (part "Res1"))
    )
    (comp (ref "R9")
      (value "205")
      (footprint "R0805")
      (description "Resistor")
      (fields (field (name "PUBLISHER") "Altium Limited"))
      (libsource (lib "*") (part "Res1"))
    )
    (comp (ref "R10")
      (value "5.11K")
      (footprint "R0805")
      (description "Resistor")
      (fields (field (name "PUBLISHER") "Altium Limited"))
      (libsource (lib "*") (part "Res1"))
    )
    (comp (ref "R11")
      (value "10K")
      (footprint "R1206")
      (description "Resistor")
      (fields (field (name "PUBLISHER") "Altium Limited"))
      (libsource (lib "*") (part "Res1"))
    )
    (comp (ref "R12")
      (value "221")
      (footprint "R0805")
      (description "Resistor")
      (fields (field (name "PUBLISHER") "Altium Limited"))
      (libsource (lib "*") (part "Res1"))
    )
    (comp (ref "R13")
      (value "511")
      (footprint "R0805")
      (description "Resistor")
      (fields (field (name "PUBLISHER") "Altium Limited"))
      (libsource (lib "*") (part "Res1"))
    )
    (comp (ref "R14")
      (value "365")
      (footprint "R0805")
      (description "Resistor")
      (fields (field (name "PUBLISHER") "Altium Limited"))
      (libsource (lib "*") (part "Res1"))
    )
    (comp (ref "R15")
      (value "196")
      (footprint "R0805")
      (description "Resistor")
      (fields (field (name "PUBLISHER") "Altium Limited"))
      (libsource (lib "*") (part "Res1"))
    )
    (comp (ref "R16")
      (value "178.4")
      (footprint "R0805")
      (description "Resistor")
      (fields (field (name "PUBLISHER") "Altium Limited"))
      (libsource (lib "*") (part "Res1"))
    )
    (comp (ref "R17")
      (value "511")
      (footprint "R0805")
      (description "Resistor")
      (fields (field (name "PUBLISHER") "Altium Limited"))
      (libsource (lib "*") (part "Res1"))
    )
    (comp (ref "R18")
      (value "309")
      (footprint "R0805")
      (description "Resistor")
      (fields (field (name "PUBLISHER") "Altium Limited"))
      (libsource (lib "*") (part "Res1"))
    )
    (comp (ref "R19")
      (value "13.3")
      (footprint "R0805")
      (description "Resistor")
      (fields (field (name "PUBLISHER") "Altium Limited"))
      (libsource (lib "*") (part "Res1"))
    )
    (comp (ref "R20")
      (value "30.1")
      (footprint "R0805")
      (description "Resistor")
      (fields (field (name "PUBLISHER") "Altium Limited"))
      (libsource (lib "*") (part "Res1"))
    )
    (comp (ref "R21")
      (value "19.6")
      (footprint "R0805")
      (description "Resistor")
      (fields (field (name "PUBLISHER") "Altium Limited"))
      (libsource (lib "*") (part "Res1"))
    )
    (comp (ref "R22")
      (value "30.1")
      (footprint "R0805")
      (description "Resistor")
      (fields (field (name "PUBLISHER") "Altium Limited"))
      (libsource (lib "*") (part "Res1"))
    )
    (comp (ref "R23")
      (value "5.11K")
      (footprint "R0805")
      (description "Resistor")
      (fields (field (name "PUBLISHER") "Altium Limited"))
      (libsource (lib "*") (part "Res1"))
    )
    (comp (ref "R24")
      (value "2K")
      (footprint "R1206")
      (description "Resistor")
      (fields (field (name "PUBLISHER") "Altium Limited"))
      (libsource (lib "*") (part "Res1"))
    )
    (comp (ref "R25")
      (value "1K")
      (footprint "R0805")
      (description "Resistor")
      (fields (field (name "PUBLISHER") "Altium Limited"))
      (libsource (lib "*") (part "Res1"))
    )
    (comp (ref "R26")
      (value "1K")
      (footprint "R0805")
      (description "Resistor")
      (fields (field (name "PUBLISHER") "Altium Limited"))
      (libsource (lib "*") (part "Res1"))
    )
    (comp (ref "R27")
      (value "100")
      (footprint "R0805")
      (description "Resistor")
      (fields (field (name "PUBLISHER") "Altium Limited"))
      (libsource (lib "*") (part "Res1"))
    )
    (comp (ref "R28")
      (value "24.9")
      (footprint "R0805")
      (description "Resistor")
      (fields (field (name "PUBLISHER") "Altium Limited"))
      (libsource (lib "*") (part "Res1"))
    )
    (comp (ref "R29")
      (value "24.9")
      (footprint "R0805")
      (description "Resistor")
      (fields (field (name "PUBLISHER") "Altium Limited"))
      (libsource (lib "*") (part "Res1"))
    )
    (comp (ref "R30")
      (value "100")
      (footprint "R0805")
      (description "Resistor")
      (fields (field (name "PUBLISHER") "Altium Limited"))
      (libsource (lib "*") (part "Res1"))
    )
    (comp (ref "R31")
      (value "0")
      (footprint "R0805")
      (description "Resistor")
      (fields (field (name "PUBLISHER") "Altium Limited"))
      (libsource (lib "*") (part "Res1"))
    )
    (comp (ref "R32")
      (value "0")
      (footprint "R0805")
      (description "Resistor")
      (fields (field (name "PUBLISHER") "Altium Limited"))
      (libsource (lib "*") (part "Res1"))
    )
    (comp (ref "R33")
      (value "1.02K")
      (footprint "R0805")
      (description "Resistor")
      (fields (field (name "PUBLISHER") "Altium Limited"))
      (libsource (lib "*") (part "Res1"))
    )
    (comp (ref "R34")
      (value "0")
      (footprint "R0805")
      (description "Resistor")
      (fields (field (name "PUBLISHER") "Altium Limited"))
      (libsource (lib "*") (part "Res1"))
    )
    (comp (ref "R35")
      (value "0")
      (footprint "R0805")
      (description "Resistor")
      (fields (field (name "PUBLISHER") "Altium Limited"))
      (libsource (lib "*") (part "Res1"))
    )
    (comp (ref "R36")
      (value "0")
      (footprint "R0805")
      (description "Resistor")
      (fields (field (name "PUBLISHER") "Altium Limited"))
      (libsource (lib "*") (part "Res1"))
    )
    (comp (ref "R37")
      (value "10")
      (footprint "R0805")
      (description "Resistor")
      (fields (field (name "PUBLISHER") "Altium Limited"))
      (libsource (lib "*") (part "Res1"))
    )
    (comp (ref "R38")
      (value "10")
      (footprint "R0805")
      (description "Resistor")
      (fields (field (name "PUBLISHER") "Altium Limited"))
      (libsource (lib "*") (part "Res1"))
    )
    (comp (ref "R39")
      (value "205")
      (footprint "R0805")
      (description "Resistor")
      (fields (field (name "PUBLISHER") "Altium Limited"))
      (libsource (lib "*") (part "Res1"))
    )
    (comp (ref "R40")
      (value "205")
      (footprint "R0805")
      (description "Resistor")
      (fields (field (name "PUBLISHER") "Altium Limited"))
      (libsource (lib "*") (part "Res1"))
    )
    (comp (ref "R41")
      (value "205")
      (footprint "R0805")
      (description "Resistor")
      (fields (field (name "PUBLISHER") "Altium Limited"))
      (libsource (lib "*") (part "Res1"))
    )
    (comp (ref "R42")
      (value "205")
      (footprint "R0805")
      (description "Resistor")
      (fields (field (name "PUBLISHER") "Altium Limited"))
      (libsource (lib "*") (part "Res1"))
    )
    (comp (ref "R43")
      (value "10.2")
      (footprint "R0805")
      (description "Resistor")
      (fields (field (name "PUBLISHER") "Altium Limited"))
      (libsource (lib "*") (part "Res1"))
    )
    (comp (ref "R44")
      (value "10.2")
      (footprint "R0805")
      (description "Resistor")
      (fields (field (name "PUBLISHER") "Altium Limited"))
      (libsource (lib "*") (part "Res1"))
    )
    (comp (ref "R45")
      (value "10.2")
      (footprint "R0805")
      (description "Resistor")
      (fields (field (name "PUBLISHER") "Altium Limited"))
      (libsource (lib "*") (part "Res1"))
    )
    (comp (ref "R46")
      (value "10.2")
      (footprint "R0805")
      (description "Resistor")
      (fields (field (name "PUBLISHER") "Altium Limited"))
      (libsource (lib "*") (part "Res1"))
    )
    (comp (ref "R47")
      (value "10.2")
      (footprint "R0805")
      (description "Resistor")
      (fields (field (name "PUBLISHER") "Altium Limited"))
      (libsource (lib "*") (part "Res1"))
    )
    (comp (ref "R48")
      (value "10.2")
      (footprint "R0805")
      (description "Resistor")
      (fields (field (name "PUBLISHER") "Altium Limited"))
      (libsource (lib "*") (part "Res1"))
    )
    (comp (ref "R49")
      (value "10.2")
      (footprint "R0805")
      (description "Resistor")
      (fields (field (name "PUBLISHER") "Altium Limited"))
      (libsource (lib "*") (part "Res1"))
    )
    (comp (ref "R50")
      (value "10.2")
      (footprint "R0805")
      (description "Resistor")
      (fields (field (name "PUBLISHER") "Altium Limited"))
      (libsource (lib "*") (part "Res1"))
    )
    (comp (ref "R51")
      (value "226")
      (footprint "R0805")
      (description "Resistor")
      (fields (field (name "PUBLISHER") "Altium Limited"))
      (libsource (lib "*") (part "Res1"))
    )
    (comp (ref "R52")
      (value "226")
      (footprint "R0805")
      (description "Resistor")
      (fields (field (name "PUBLISHER") "Altium Limited"))
      (libsource (lib "*") (part "Res1"))
    )
    (comp (ref "R53")
      (value "4.02K")
      (footprint "R0805")
      (description "Resistor")
      (fields (field (name "PUBLISHER") "Altium Limited"))
      (libsource (lib "*") (part "Res1"))
    )
    (comp (ref "R54")
      (value "4.02K")
      (footprint "R0805")
      (description "Resistor")
      (fields (field (name "PUBLISHER") "Altium Limited"))
      (libsource (lib "*") (part "Res1"))
    )
    (comp (ref "R55")
      (value "100")
      (footprint "R0805")
      (description "Resistor")
      (fields (field (name "PUBLISHER") "Altium Limited"))
      (libsource (lib "*") (part "Res1"))
    )
    (comp (ref "R56")
      (value "100")
      (footprint "R0805")
      (description "Resistor")
      (fields (field (name "PUBLISHER") "Altium Limited"))
      (libsource (lib "*") (part "Res1"))
    )
    (comp (ref "R57")
      (value "10.2")
      (footprint "R0805")
      (description "Resistor")
      (fields (field (name "PUBLISHER") "Altium Limited"))
      (libsource (lib "*") (part "Res1"))
    )
    (comp (ref "R58")
      (value "953")
      (footprint "R0805")
      (description "Resistor")
      (fields (field (name "PUBLISHER") "Altium Limited"))
      (libsource (lib "*") (part "Res1"))
    )
    (comp (ref "R59")
      (value "10.2")
      (footprint "R0805")
      (description "Resistor")
      (fields (field (name "PUBLISHER") "Altium Limited"))
      (libsource (lib "") (part "Res1_1"))
    )
    (comp (ref "R61")
      (value "10.2")
      (footprint "R0805")
      (description "Resistor")
      (fields (field (name "PUBLISHER") "Altium Limited"))
      (libsource (lib "*") (part "Res1"))
    )
    (comp (ref "R62")
      (value "0")
      (footprint "R0805")
      (description "Resistor")
      (fields (field (name "PUBLISHER") "Altium Limited"))
      (libsource (lib "*") (part "Res1"))
    )
    (comp (ref "R63")
      (value "49.9")
      (footprint "R0805")
      (description "Resistor")
      (fields (field (name "PUBLISHER") "Altium Limited"))
      (libsource (lib "*") (part "Res1"))
    )
    (comp (ref "R64")
      (value "49.9")
      (footprint "R0805")
      (description "Resistor")
      (fields (field (name "PUBLISHER") "Altium Limited"))
      (libsource (lib "*") (part "Res1"))
    )
    (comp (ref "R65")
      (value "10.2")
      (footprint "R0805")
      (description "Resistor")
      (fields (field (name "PUBLISHER") "Altium Limited"))
      (libsource (lib "") (part "Res1_1"))
    )
    (comp (ref "R67")
      (value "0")
      (footprint "R0805")
      (description "Resistor")
      (fields (field (name "PUBLISHER") "Altium Limited"))
      (libsource (lib "Miscellaneous Devices") (part "Res1"))
    )
    (comp (ref "R69")
      (value "0")
      (footprint "R0805")
      (description "Resistor")
      (fields (field (name "PUBLISHER") "Altium Limited"))
      (libsource (lib "Miscellaneous Devices") (part "Res1"))
    )
    (comp (ref "R71")
      (value "1.05K")
      (footprint "R0805")
      (description "Resistor")
      (fields (field (name "PUBLISHER") "Altium Limited"))
      (libsource (lib "Miscellaneous Devices") (part "Res1"))
    )
    (comp (ref "R72")
      (value "226")
      (footprint "R0805")
      (description "Resistor")
      (fields (field (name "PUBLISHER") "Altium Limited"))
      (libsource (lib "Miscellaneous Devices") (part "Res1"))
    )
    (comp (ref "T1") (value "Tran2") (footprint "Tran2") (libsource (lib "*") (part "Tran2")))
    (comp (ref "T2") (value "Tran3") (footprint "Tran3") (libsource (lib "*") (part "Tran3")))
    (comp (ref "T3") (value "Tran2") (footprint "Tran2") (libsource (lib "*") (part "Tran2")))
    (comp (ref "T4") (value "Tran3") (footprint "Tran3") (libsource (lib "*") (part "Tran3")))
    (comp (ref "TP1") (value "TestPoint") (footprint "test_small") (libsource (lib "") (part "TestPoint_1")))
    (comp (ref "TP2") (value "TestPoint") (footprint "test_small") (libsource (lib "") (part "TestPoint_1")))
    (comp (ref "TP3") (value "TestPoint") (footprint "test_small") (libsource (lib "") (part "TestPoint_1")))
    (comp (ref "TP4") (value "TestPoint") (footprint "test_small") (libsource (lib "") (part "TestPoint_1")))
    (comp (ref "TP5") (value "TestPoint") (footprint "test_small") (libsource (lib "") (part "TestPoint_1")))
    (comp (ref "TP6") (value "TestPoint") (footprint "test_small") (libsource (lib "*") (part "TestPoint")))
    (comp (ref "TP7") (value "TestPoint") (footprint "test_small") (libsource (lib "") (part "TestPoint_1")))
    (comp (ref "TP8") (value "TestPoint") (footprint "test_small") (libsource (lib "") (part "TestPoint_1")))
    (comp (ref "TP9") (value "TestPoint") (footprint "test_small") (libsource (lib "") (part "TestPoint_1")))
    (comp (ref "TP10") (value "TestPoint") (footprint "test_small") (libsource (lib "") (part "TestPoint_1")))
    (comp (ref "TP11") (value "TestPoint") (footprint "test_small") (libsource (lib "") (part "TestPoint_1")))
    (comp (ref "TP12") (value "TestPoint") (footprint "test_small") (libsource (lib "*") (part "TestPoint")))
    (comp (ref "TP13") (value "TestPoint") (footprint "test_small") (libsource (lib "*") (part "TestPoint")))
    (comp (ref "TP14") (value "TestPoint") (footprint "test_small") (libsource (lib "*") (part "TestPoint")))
    (comp (ref "TP15") (value "TestPoint") (footprint "test_small") (libsource (lib "*") (part "TestPoint")))
    (comp (ref "TP16") (value "TestPoint") (footprint "test_small") (libsource (lib "") (part "TestPoint_1")))
    (comp (ref "TP17") (value "TestPoint") (footprint "test_small") (libsource (lib "") (part "TestPoint_1")))
    (comp (ref "TP18") (value "TestPoint") (footprint "test_small") (libsource (lib "") (part "TestPoint_1")))
    (comp (ref "TP19") (value "TestPoint") (footprint "test_small") (libsource (lib "") (part "TestPoint_1")))
    (comp (ref "TP20") (value "TestPoint") (footprint "test_small") (libsource (lib "") (part "TestPoint_1")))
    (comp (ref "TP21") (value "TestPoint") (footprint "test_small") (libsource (lib "") (part "TestPoint_1")))
    (comp (ref "TP23") (value "TestPoint") (footprint "test_small") (libsource (lib "*") (part "TestPoint")))
    (comp (ref "U1")
      (value "DS26C32AMJ/883_DIP16")
      (footprint "DIP16")
      (libsource (lib "*") (part "DS26LV32AM"))
    )
    (comp (ref "U2")
      (value "CD54ACT00F3A_DIP14")
      (footprint "DIP14")
      (libsource (lib "PreAmp") (part "SNJ54ACT00W"))
    )
    (comp (ref "U3")
      (value "SNJ54ACT04W_DIP14")
      (footprint "DIP14")
      (description "Hex Inverter")
      (libsource (lib "PreAmp") (part "SNJ54ACT04W"))
    )
    (comp (ref "U4")
      (value "AD790SQ")
      (footprint "DIP8")
      (description "fast,precision comparator")
      (fields (field (name "PUBLISHER") "Altium Limited"))
      (libsource (lib "AD Operational Amplifier") (part "AD790SQ"))
    )
    (comp (ref "U5") (value "TC4429EOA") (footprint "SO-8") (libsource (lib "*") (part "TC4429EOA")))
    (comp (ref "U6") (value "TC4429EOA") (footprint "SO-8") (libsource (lib "*") (part "TC4429EOA")))
    (comp (ref "U7") (value "TC4429EOA") (footprint "SO-8") (libsource (lib "*") (part "TC4429EOA")))
    (comp (ref "U8") (value "TC4429EOA") (footprint "SO-8") (libsource (lib "*") (part "TC4429EOA")))
    (comp (ref "U9")
      (value "AD790SQ")
      (footprint "DIP8")
      (description "fast,precision comparator")
      (fields (field (name "PUBLISHER") "Altium Limited"))
      (libsource (lib "AD Operational Amplifier") (part "AD790SQ"))
    )
    (comp (ref "U10") (value "AD797_DIP8") (footprint "DIP8") (libsource (lib "*") (part "AD797")))
    (comp (ref "U11") (value "AD797_DIP8") (footprint "DIP8") (libsource (lib "*") (part "AD797")))
    (comp (ref "U12") (value "AD797_DIP8") (footprint "DIP8") (libsource (lib "*") (part "AD797")))
    (comp (ref "U13") (value "AD797_DIP8") (footprint "DIP8") (libsource (lib "*") (part "AD797")))
    (comp (ref "U14") (value "AD8130_SO-8") (footprint "SO-8") (libsource (lib "*") (part "AD8130")))
    (comp (ref "U15") (value "AD8130_SO-8") (footprint "SO-8") (libsource (lib "*") (part "AD8130")))
    (comp (ref "U16") (value "AD797_DIP8") (footprint "DIP8") (libsource (lib "*") (part "AD797")))
    (comp (ref "U17") (value "LTC1560-1_SO-8") (footprint "SO-8") (libsource (lib "*") (part "LTC1560")))
    (comp (ref "U18") (value "AD8131_SO-8") (footprint "SO-8") (libsource (lib "*") (part "AD8131")))
    (comp (ref "U19") (value "AD797_DIP8") (footprint "DIP8") (libsource (lib "*") (part "AD797")))
  )
  (nets
    (net (code "1") (name "+5D") (class "Default")
      (node (ref "C14") (pin "2") (pinfunction "2_2") (pintype "passive"))
      (node (ref "C17") (pin "1") (pinfunction "1_1") (pintype "passive"))
      (node (ref "C18") (pin "1") (pinfunction "1_1") (pintype "passive"))
      (node (ref "C19") (pin "2") (pinfunction "2_2") (pintype "passive"))
      (node (ref "C22") (pin "1") (pinfunction "1_1") (pintype "passive"))
      (node (ref "C23") (pin "1") (pinfunction "1_1") (pintype "passive"))
      (node (ref "C24") (pin "1") (pinfunction "1_1") (pintype "passive"))
      (node (ref "C25") (pin "1") (pinfunction "1_1") (pintype "passive"))
      (node (ref "C26") (pin "2") (pinfunction "2_2") (pintype "passive"))
      (node (ref "C27") (pin "2") (pinfunction "2_2") (pintype "passive"))
      (node (ref "C28") (pin "2") (pinfunction "2_2") (pintype "passive"))
      (node (ref "C29") (pin "2") (pinfunction "2_2") (pintype "passive"))
      (node (ref "C3") (pin "1") (pinfunction "1_1") (pintype "passive"))
      (node (ref "C30") (pin "2") (pinfunction "2_2") (pintype "passive"))
      (node (ref "C31") (pin "1") (pinfunction "1_1") (pintype "passive"))
      (node (ref "C4") (pin "1") (pinfunction "1_1") (pintype "passive"))
      (node (ref "C7") (pin "2") (pinfunction "2_2") (pintype "passive"))
      (node (ref "D14") (pin "2") (pintype "passive"))
      (node (ref "D15") (pin "2") (pintype "passive"))
      (node (ref "D16") (pin "2") (pintype "passive"))
      (node (ref "D17") (pin "2") (pintype "passive"))
      (node (ref "E10") (pin "1") (pinfunction "NC_1") (pintype "passive"))
      (node (ref "R10") (pin "2") (pinfunction "2_2") (pintype "passive"))
      (node (ref "R13") (pin "2") (pinfunction "2_2") (pintype "passive"))
      (node (ref "R17") (pin "2") (pinfunction "2_2") (pintype "passive"))
      (node (ref "R23") (pin "2") (pinfunction "2_2") (pintype "passive"))
      (node (ref "T1") (pin "4") (pinfunction "Pri-_4") (pintype "passive"))
      (node (ref "T2") (pin "6") (pinfunction "Pri+_6") (pintype "passive"))
      (node (ref "T3") (pin "4") (pinfunction "Pri-_4") (pintype "passive"))
      (node (ref "T4") (pin "6") (pinfunction "Pri+_6") (pintype "passive"))
      (node (ref "U1") (pin "16") (pinfunction "VCC_16") (pintype "passive"))
      (node (ref "U1") (pin "4") (pinfunction "ENABLE_4") (pintype "passive"))
      (node (ref "U2") (pin "14") (pinfunction "Vcc_14") (pintype "power_in"))
      (node (ref "U3") (pin "14") (pinfunction "Vcc_14") (pintype "power_in"))
      (node (ref "U4") (pin "1") (pinfunction "+Vs_1") (pintype "power_in"))
      (node (ref "U4") (pin "8") (pinfunction "Vlogic_8") (pintype "passive"))
      (node (ref "U5") (pin "1") (pinfunction "VDD1_1") (pintype "passive"))
      (node (ref "U5") (pin "8") (pinfunction "VDD2_8") (pintype "passive"))
      (node (ref "U6") (pin "1") (pinfunction "VDD1_1") (pintype "passive"))
      (node (ref "U6") (pin "8") (pinfunction "VDD2_8") (pintype "passive"))
      (node (ref "U7") (pin "1") (pinfunction "VDD1_1") (pintype "passive"))
      (node (ref "U7") (pin "8") (pinfunction "VDD2_8") (pintype "passive"))
      (node (ref "U8") (pin "1") (pinfunction "VDD1_1") (pintype "passive"))
      (node (ref "U8") (pin "8") (pinfunction "VDD2_8") (pintype "passive"))
      (node (ref "U9") (pin "1") (pinfunction "+Vs_1") (pintype "power_in"))
      (node (ref "U9") (pin "8") (pinfunction "Vlogic_8") (pintype "passive"))
    )
    (net (code "2") (name "+5V") (class "Default")
      (node (ref "C75") (pin "1") (pinfunction "1_1") (pintype "passive"))
      (node (ref "C76") (pin "1") (pinfunction "1_1") (pintype "passive"))
      (node (ref "D36") (pin "3") (pinfunction "A_3") (pintype "passive"))
      (node (ref "D8") (pin "2") (pinfunction "K_2") (pintype "passive"))
      (node (ref "U17") (pin "6") (pinfunction "V+_6") (pintype "passive"))
    )
    (net (code "3") (name "+8V") (class "Default")
      (node (ref "C10") (pin "1") (pinfunction "1_1") (pintype "passive"))
      (node (ref "C5") (pin "1") (pinfunction "1_1") (pintype "passive"))
      (node (ref "C65") (pin "1") (pinfunction "1_1") (pintype "passive"))
      (node (ref "C66") (pin "2") (pinfunction "2_2") (pintype "passive"))
      (node (ref "C69") (pin "1") (pinfunction "1_1") (pintype "passive"))
      (node (ref "C70") (pin "2") (pinfunction "2_2") (pintype "passive"))
      (node (ref "C8") (pin "1") (pinfunction "1_1") (pintype "passive"))
      (node (ref "D6") (pin "3") (pinfunction "A_3") (pintype "passive"))
      (node (ref "E7") (pin "1") (pinfunction "NC_1") (pintype "passive"))
      (node (ref "R43") (pin "2") (pinfunction "2_2") (pintype "passive"))
      (node (ref "R44") (pin "2") (pinfunction "2_2") (pintype "passive"))
      (node (ref "R49") (pin "2") (pinfunction "2_2") (pintype "passive"))
      (node (ref "R50") (pin "2") (pinfunction "2_2") (pintype "passive"))
      (node (ref "R59") (pin "2") (pinfunction "2_2") (pintype "passive"))
      (node (ref "R65") (pin "2") (pinfunction "2_2") (pintype "passive"))
      (node (ref "U14") (pin "3") (pinfunction "~{PD}_3") (pintype "power_in"))
      (node (ref "U14") (pin "7") (pinfunction "+VS_7") (pintype "power_in"))
      (node (ref "U15") (pin "3") (pinfunction "~{PD}_3") (pintype "power_in"))
      (node (ref "U15") (pin "7") (pinfunction "+VS_7") (pintype "power_in"))
    )
    (net (code "4") (name "-5V") (class "Default")
      (node (ref "C79") (pin "1") (pinfunction "1_1") (pintype "passive"))
      (node (ref "C80") (pin "1") (pinfunction "1_1") (pintype "passive"))
      (node (ref "D11") (pin "3") (pinfunction "A_3") (pintype "passive"))
      (node (ref "D37") (pin "2") (pinfunction "K_2") (pintype "passive"))
      (node (ref "U17") (pin "4") (pinfunction "V-_4") (pintype "passive"))
      (node (ref "U17") (pin "5") (pinfunction "~{FC}_5") (pintype "passive"))
    )
    (net (code "5") (name "-8V") (class "Default")
      (node (ref "C11") (pin "1") (pinfunction "1_1") (pintype "passive"))
      (node (ref "C6") (pin "2") (pinfunction "2_2") (pintype "passive"))
      (node (ref "C67") (pin "2") (pinfunction "2_2") (pintype "passive"))
      (node (ref "C68") (pin "2") (pinfunction "2_2") (pintype "passive"))
      (node (ref "C71") (pin "2") (pinfunction "2_2") (pintype "passive"))
      (node (ref "C72") (pin "2") (pinfunction "2_2") (pintype "passive"))
      (node (ref "C9") (pin "2") (pinfunction "2_2") (pintype "passive"))
      (node (ref "D9") (pin "2") (pinfunction "K_2") (pintype "passive"))
      (node (ref "E9") (pin "1") (pinfunction "NC_1") (pintype "passive"))
      (node (ref "R45") (pin "2") (pinfunction "2_2") (pintype "passive"))
      (node (ref "R46") (pin "2") (pinfunction "2_2") (pintype "passive"))
      (node (ref "R47") (pin "2") (pinfunction "2_2") (pintype "passive"))
      (node (ref "R48") (pin "2") (pinfunction "2_2") (pintype "passive"))
      (node (ref "R57") (pin "2") (pinfunction "2_2") (pintype "passive"))
      (node (ref "R61") (pin "2") (pinfunction "2_2") (pintype "passive"))
      (node (ref "U14") (pin "2") (pinfunction "-VS_2") (pintype "power_in"))
      (node (ref "U15") (pin "2") (pinfunction "-VS_2") (pintype "power_in"))
    )
    (net (code "6") (name "/AntennaEcho+") (class "Default")
      (node (ref "E6") (pin "1") (pinfunction "NC_1") (pintype "passive"))
      (node (ref "Q4") (pin "2") (pinfunction "D_2") (pintype "passive"))
      (node (ref "R6") (pin "1") (pinfunction "1_1") (pintype "passive"))
    )
    (net (code "7") (name "/AntennaEcho-") (class "Default")
      (node (ref "E5") (pin "1") (pinfunction "NC_1") (pintype "passive"))
      (node (ref "Q3") (pin "2") (pinfunction "D_2") (pintype "passive"))
      (node (ref "R5") (pin "1") (pinfunction "1_1") (pintype "passive"))
    )
    (net (code "8") (name "/PreAmpEcho+") (class "Default")
      (node (ref "E12") (pin "1") (pinfunction "NC_1") (pintype "passive"))
      (node (ref "R63") (pin "2") (pinfunction "2_2") (pintype "passive"))
      (node (ref "TP20") (pin "1") (pinfunction "NC_1") (pintype "passive"))
    )
    (net (code "9") (name "/PreAmpEcho-") (class "Default")
      (node (ref "E13") (pin "1") (pinfunction "NC_1") (pintype "passive"))
      (node (ref "R64") (pin "2") (pinfunction "2_2") (pintype "passive"))
      (node (ref "TP21") (pin "1") (pinfunction "NC_1") (pintype "passive"))
    )
    (net (code "10") (name "/Prj") (class "Default")
      (node (ref "TP3") (pin "1") (pinfunction "NC_1") (pintype "passive"))
      (node (ref "U2") (pin "10") (pinfunction "A_10") (pintype "input"))
      (node (ref "U3") (pin "6") (pinfunction "~{O}_6") (pintype "output"))
    )
    (net (code "11") (name "/RT_SW+") (class "Default")
      (node (ref "C1") (pin "2") (pinfunction "2_2") (pintype "passive"))
      (node (ref "E1") (pin "1") (pinfunction "NC_1") (pintype "passive"))
      (node (ref "R1") (pin "1") (pinfunction "1_1") (pintype "passive"))
    )
    (net (code "12") (name "/RT_SW-") (class "Default")
      (node (ref "C1") (pin "1") (pinfunction "1_1") (pintype "passive"))
      (node (ref "E2") (pin "1") (pinfunction "NC_1") (pintype "passive"))
      (node (ref "R2") (pin "1") (pinfunction "1_1") (pintype "passive"))
    )
    (net (code "13") (name "/SIGNAL") (class "Default")
      (node (ref "C94") (pin "1") (pinfunction "1_1") (pintype "passive"))
      (node (ref "R62") (pin "2") (pinfunction "2_2") (pintype "passive"))
      (node (ref "R72") (pin "2") (pinfunction "2_2") (pintype "passive"))
      (node (ref "TP17") (pin "1") (pinfunction "NC_1") (pintype "passive"))
      (node (ref "U17") (pin "2") (pinfunction "VI_2") (pintype "passive"))
      (node (ref "U19") (pin "6") (pinfunction "OUTPUT_6") (pintype "output"))
    )
    (net (code "14") (name "/SoftDump+") (class "Default")
      (node (ref "C2") (pin "2") (pinfunction "2_2") (pintype "passive"))
      (node (ref "E3") (pin "1") (pinfunction "NC_1") (pintype "passive"))
      (node (ref "R3") (pin "1") (pinfunction "1_1") (pintype "passive"))
    )
    (net (code "15") (name "/SoftDump-") (class "Default")
      (node (ref "C2") (pin "1") (pinfunction "1_1") (pintype "passive"))
      (node (ref "E4") (pin "1") (pinfunction "NC_1") (pintype "passive"))
      (node (ref "R4") (pin "1") (pinfunction "1_1") (pintype "passive"))
    )
    (net (code "16") (name "/Unexpect_HV") (class "Default")
      (node (ref "TP6") (pin "1") (pinfunction "NC_1") (pintype "passive"))
      (node (ref "U2") (pin "2") (pinfunction "B_2") (pintype "input"))
      (node (ref "U9") (pin "7") (pinfunction "OUT_7") (pintype "output"))
    )
    (net (code "17") (name "AGND") (class "Default")
      (node (ref "C10") (pin "2") (pinfunction "2_2") (pintype "passive"))
      (node (ref "C11") (pin "2") (pinfunction "2_2") (pintype "passive"))
      (node (ref "C41") (pin "1") (pinfunction "1_1") (pintype "passive"))
      (node (ref "C42") (pin "1") (pinfunction "1_1") (pintype "passive"))
      (node (ref "C43") (pin "1") (pinfunction "1_1") (pintype "passive"))
      (node (ref "C44") (pin "1") (pinfunction "1_1") (pintype "passive"))
      (node (ref "C45") (pin "2") (pinfunction "2_2") (pintype "passive"))
      (node (ref "C46") (pin "1") (pinfunction "1_1") (pintype "passive"))
      (node (ref "C47") (pin "1") (pinfunction "1_1") (pintype "passive"))
      (node (ref "C48") (pin "1") (pinfunction "1_1") (pintype "passive"))
      (node (ref "C5") (pin "2") (pinfunction "2_2") (pintype "passive"))
      (node (ref "C51") (pin "2") (pinfunction "2_2") (pintype "passive"))
      (node (ref "C54") (pin "1") (pinfunction "1_1") (pintype "passive"))
      (node (ref "C55") (pin "1") (pinfunction "1_1") (pintype "passive"))
      (node (ref "C56") (pin "2") (pinfunction "2_2") (pintype "passive"))
      (node (ref "C57") (pin "2") (pinfunction "2_2") (pintype "passive"))
      (node (ref "C58") (pin "2") (pinfunction "2_2") (pintype "passive"))
      (node (ref "C59") (pin "2") (pinfunction "2_2") (pintype "passive"))
      (node (ref "C6") (pin "1") (pinfunction "1_1") (pintype "passive"))
      (node (ref "C60") (pin "2") (pinfunction "2_2") (pintype "passive"))
      (node (ref "C65") (pin "2") (pinfunction "2_2") (pintype "passive"))
      (node (ref "C66") (pin "1") (pinfunction "1_1") (pintype "passive"))
      (node (ref "C67") (pin "1") (pinfunction "1_1") (pintype "passive"))
      (node (ref "C68") (pin "1") (pinfunction "1_1") (pintype "passive"))
      (node (ref "C69") (pin "2") (pinfunction "2_2") (pintype "passive"))
      (node (ref "C70") (pin "1") (pinfunction "1_1") (pintype "passive"))
      (node (ref "C71") (pin "1") (pinfunction "1_1") (pintype "passive"))
      (node (ref "C72") (pin "1") (pinfunction "1_1") (pintype "passive"))
      (node (ref "C75") (pin "2") (pinfunction "2_2") (pintype "passive"))
      (node (ref "C76") (pin "2") (pinfunction "2_2") (pintype "passive"))
      (node (ref "C77") (pin "1") (pinfunction "1_1") (pintype "passive"))
      (node (ref "C78") (pin "1") (pinfunction "1_1") (pintype "passive"))
      (node (ref "C79") (pin "2") (pinfunction "2_2") (pintype "passive"))
      (node (ref "C8") (pin "2") (pinfunction "2_2") (pintype "passive"))
      (node (ref "C80") (pin "2") (pinfunction "2_2") (pintype "passive"))
      (node (ref "C82") (pin "2") (pinfunction "2_2") (pintype "passive"))
      (node (ref "C84") (pin "2") (pinfunction "2_2") (pintype "passive"))
      (node (ref "C86") (pin "1") (pinfunction "1_1") (pintype "passive"))
      (node (ref "C87") (pin "1") (pinfunction "1_1") (pintype "passive"))
      (node (ref "C88") (pin "2") (pinfunction "2_2") (pintype "passive"))
      (node (ref "C89") (pin "2") (pinfunction "2_2") (pintype "passive"))
      (node (ref "C9") (pin "1") (pinfunction "1_1") (pintype "passive"))
      (node (ref "C90") (pin "1") (pinfunction "1_1") (pintype "passive"))
      (node (ref "C91") (pin "2") (pinfunction "2_2") (pintype "passive"))
      (node (ref "C93") (pin "2") (pinfunction "2_2") (pintype "passive"))
      (node (ref "C95") (pin "2") (pinfunction "2_2") (pintype "passive"))
      (node (ref "D30") (pin "2") (pinfunction "A_2") (pintype "passive"))
      (node (ref "D31") (pin "2") (pinfunction "A_2") (pintype "passive"))
      (node (ref "D32") (pin "1") (pinfunction "K_1") (pintype "passive"))
      (node (ref "D33") (pin "1") (pinfunction "K_1") (pintype "passive"))
      (node (ref "E8") (pin "1") (pinfunction "NC_1") (pintype "passive"))
      (node (ref "R51") (pin "2") (pinfunction "2_2") (pintype "passive"))
      (node (ref "R52") (pin "2") (pinfunction "2_2") (pintype "passive"))
      (node (ref "R69") (pin "2") (pinfunction "2_2") (pintype "passive"))
      (node (ref "R71") (pin "1") (pinfunction "1_1") (pintype "passive"))
      (node (ref "U14") (pin "4") (pinfunction "REF_4") (pintype "power_in"))
      (node (ref "U15") (pin "4") (pinfunction "REF_4") (pintype "power_in"))
      (node (ref "U17") (pin "1") (pinfunction "GND1_1") (pintype "passive"))
      (node (ref "U17") (pin "3") (pinfunction "GND2_3") (pintype "passive"))
      (node (ref "U17") (pin "7") (pinfunction "SHDN_7") (pintype "passive"))
      (node (ref "U18") (pin "1") (pinfunction "Din-_1") (pintype "input"))
      (node (ref "U18") (pin "2") (pinfunction "Vcom_2") (pintype "passive"))
    )
    (net (code "18") (name "DGND") (class "Default")
      (node (ref "C12") (pin "1") (pinfunction "1_1") (pintype "passive"))
      (node (ref "C13") (pin "2") (pinfunction "2_2") (pintype "passive"))
      (node (ref "C14") (pin "1") (pinfunction "1_1") (pintype "passive"))
      (node (ref "C15") (pin "1") (pinfunction "1_1") (pintype "passive"))
      (node (ref "C16") (pin "2") (pinfunction "2_2") (pintype "passive"))
      (node (ref "C17") (pin "2") (pinfunction "2_2") (pintype "passive"))
      (node (ref "C18") (pin "2") (pinfunction "2_2") (pintype "passive"))
      (node (ref "C19") (pin "1") (pinfunction "1_1") (pintype "passive"))
      (node (ref "C22") (pin "2") (pinfunction "2_2") (pintype "passive"))
      (node (ref "C23") (pin "2") (pinfunction "2_2") (pintype "passive"))
      (node (ref "C24") (pin "2") (pinfunction "2_2") (pintype "passive"))
      (node (ref "C25") (pin "2") (pinfunction "2_2") (pintype "passive"))
      (node (ref "C26") (pin "1") (pinfunction "1_1") (pintype "passive"))
      (node (ref "C27") (pin "1") (pinfunction "1_1") (pintype "passive"))
      (node (ref "C28") (pin "1") (pinfunction "1_1") (pintype "passive"))
      (node (ref "C29") (pin "1") (pinfunction "1_1") (pintype "passive"))
      (node (ref "C3") (pin "2") (pinfunction "2_2") (pintype "passive"))
      (node (ref "C30") (pin "1") (pinfunction "1_1") (pintype "passive"))
      (node (ref "C31") (pin "2") (pinfunction "2_2") (pintype "passive"))
      (node (ref "C32") (pin "1") (pinfunction "1_1") (pintype "passive"))
      (node (ref "C33") (pin "1") (pinfunction "1_1") (pintype "passive"))
      (node (ref "C36") (pin "2") (pinfunction "2_2") (pintype "passive"))
      (node (ref "C4") (pin "2") (pinfunction "2_2") (pintype "passive"))
      (node (ref "C7") (pin "1") (pinfunction "1_1") (pintype "passive"))
      (node (ref "D12") (pin "1") (pinfunction "A_1") (pintype "passive"))
      (node (ref "D13") (pin "1") (pinfunction "A_1") (pintype "passive"))
      (node (ref "D5") (pin "2") (pintype "passive"))
      (node (ref "E11") (pin "1") (pinfunction "NC_1") (pintype "passive"))
      (node (ref "R11") (pin "1") (pinfunction "1_1") (pintype "passive"))
      (node (ref "R12") (pin "2") (pinfunction "2_2") (pintype "passive"))
      (node (ref "R15") (pin "1") (pinfunction "1_1") (pintype "passive"))
      (node (ref "R16") (pin "1") (pinfunction "1_1") (pintype "passive"))
      (node (ref "R18") (pin "2") (pinfunction "2_2") (pintype "passive"))
      (node (ref "R24") (pin "2") (pinfunction "2_2") (pintype "passive"))
      (node (ref "R33") (pin "1") (pinfunction "1_1") (pintype "passive"))
      (node (ref "R36") (pin "2") (pinfunction "2_2") (pintype "passive"))
      (node (ref "R7") (pin "1") (pinfunction "1_1") (pintype "passive"))
      (node (ref "R8") (pin "1") (pinfunction "1_1") (pintype "passive"))
      (node (ref "U1") (pin "12") (pinfunction "~{ENABLE}_12") (pintype "passive"))
      (node (ref "U1") (pin "8") (pinfunction "GND_8") (pintype "passive"))
      (node (ref "U2") (pin "4") (pinfunction "A_4") (pintype "input"))
      (node (ref "U2") (pin "5") (pinfunction "B_5") (pintype "input"))
      (node (ref "U2") (pin "7") (pinfunction "GND_7") (pintype "power_in"))
      (node (ref "U3") (pin "1") (pinfunction "A_1") (pintype "input"))
      (node (ref "U3") (pin "13") (pinfunction "A_13") (pintype "input"))
      (node (ref "U3") (pin "3") (pinfunction "A_3") (pintype "input"))
      (node (ref "U3") (pin "7") (pinfunction "GND_7") (pintype "power_in"))
      (node (ref "U4") (pin "4") (pinfunction "-Vs_4") (pintype "power_in"))
      (node (ref "U4") (pin "6") (pinfunction "GND_6") (pintype "power_in"))
      (node (ref "U5") (pin "4") (pinfunction "GND1_4") (pintype "passive"))
      (node (ref "U5") (pin "5") (pinfunction "GND2_5") (pintype "passive"))
      (node (ref "U6") (pin "4") (pinfunction "GND1_4") (pintype "passive"))
      (node (ref "U6") (pin "5") (pinfunction "GND2_5") (pintype "passive"))
      (node (ref "U7") (pin "4") (pinfunction "GND1_4") (pintype "passive"))
      (node (ref "U7") (pin "5") (pinfunction "GND2_5") (pintype "passive"))
      (node (ref "U8") (pin "4") (pinfunction "GND1_4") (pintype "passive"))
      (node (ref "U8") (pin "5") (pinfunction "GND2_5") (pintype "passive"))
      (node (ref "U9") (pin "4") (pinfunction "-Vs_4") (pintype "power_in"))
      (node (ref "U9") (pin "6") (pinfunction "GND_6") (pintype "power_in"))
    )
    (net (code "19") (name "Net-(C36-Pad1)") (class "Default")
      (node (ref "C36") (pin "1") (pinfunction "1_1") (pintype "passive"))
      (node (ref "R27") (pin "2") (pinfunction "2_2") (pintype "passive"))
      (node (ref "R30") (pin "1") (pinfunction "1_1") (pintype "passive"))
    )
    (net (code "20") (name "Net-(C39-Pad1)") (class "Default")
      (node (ref "C39") (pin "1") (pinfunction "1_1") (pintype "passive"))
      (node (ref "R37") (pin "1") (pinfunction "1_1") (pintype "passive"))
    )
    (net (code "21") (name "Net-(C40-Pad1)") (class "Default")
      (node (ref "C40") (pin "1") (pinfunction "1_1") (pintype "passive"))
      (node (ref "R38") (pin "1") (pinfunction "1_1") (pintype "passive"))
    )
    (net (code "22") (name "Net-(C51-Pad1)") (class "Default")
      (node (ref "C51") (pin "1") (pinfunction "1_1") (pintype "passive"))
      (node (ref "C54") (pin "2") (pinfunction "2_2") (pintype "passive"))
      (node (ref "R49") (pin "1") (pinfunction "1_1") (pintype "passive"))
      (node (ref "U12") (pin "7") (pinfunction "NC_7") (pintype "power_in"))
    )
    (net (code "23") (name "Net-(C55-Pad2)") (class "Default")
      (node (ref "C55") (pin "2") (pinfunction "2_2") (pintype "passive"))
      (node (ref "C56") (pin "1") (pinfunction "1_1") (pintype "passive"))
      (node (ref "R50") (pin "1") (pinfunction "1_1") (pintype "passive"))
      (node (ref "U13") (pin "7") (pinfunction "NC_7") (pintype "power_in"))
    )
    (net (code "24") (name "Net-(C57-Pad1)") (class "Default")
      (node (ref "C57") (pin "1") (pinfunction "1_1") (pintype "passive"))
      (node (ref "C58") (pin "1") (pinfunction "1_1") (pintype "passive"))
      (node (ref "R43") (pin "1") (pinfunction "1_1") (pintype "passive"))
      (node (ref "U10") (pin "7") (pinfunction "NC_7") (pintype "power_in"))
    )
    (net (code "25") (name "Net-(C59-Pad1)") (class "Default")
      (node (ref "C59") (pin "1") (pinfunction "1_1") (pintype "passive"))
      (node (ref "C60") (pin "1") (pinfunction "1_1") (pintype "passive"))
      (node (ref "R44") (pin "1") (pinfunction "1_1") (pintype "passive"))
      (node (ref "U11") (pin "7") (pinfunction "NC_7") (pintype "power_in"))
    )
    (net (code "26") (name "Net-(C73-Pad1)") (class "Default")
      (node (ref "C73") (pin "1") (pinfunction "1_1") (pintype "passive"))
      (node (ref "R55") (pin "1") (pinfunction "1_1") (pintype "passive"))
    )
    (net (code "27") (name "Net-(C74-Pad1)") (class "Default")
      (node (ref "C74") (pin "1") (pinfunction "1_1") (pintype "passive"))
      (node (ref "R56") (pin "1") (pinfunction "1_1") (pintype "passive"))
    )
    (net (code "28") (name "Net-(C82-Pad1)") (class "Default")
      (node (ref "C82") (pin "1") (pinfunction "1_1") (pintype "passive"))
      (node (ref "C84") (pin "1") (pinfunction "1_1") (pintype "passive"))
      (node (ref "R59") (pin "1") (pinfunction "1_1") (pintype "passive"))
      (node (ref "U16") (pin "7") (pinfunction "NC_7") (pintype "power_in"))
    )
    (net (code "29") (name "Net-(C85-Pad1)") (class "Default")
      (node (ref "C85") (pin "1") (pinfunction "1_1") (pintype "passive"))
      (node (ref "C97") (pin "1") (pinfunction "1_1") (pintype "passive"))
      (node (ref "R72") (pin "1") (pinfunction "1_1") (pintype "passive"))
    )
    (net (code "30") (name "Net-(C93-Pad1)") (class "Default")
      (node (ref "C93") (pin "1") (pinfunction "1_1") (pintype "passive"))
      (node (ref "C95") (pin "1") (pinfunction "1_1") (pintype "passive"))
      (node (ref "R65") (pin "1") (pinfunction "1_1") (pintype "passive"))
      (node (ref "U19") (pin "7") (pinfunction "NC_7") (pintype "power_in"))
    )
    (net (code "31") (name "Net-(D1-A)") (class "Default")
      (node (ref "D1") (pin "1") (pinfunction "A_1") (pintype "passive"))
      (node (ref "R5") (pin "2") (pinfunction "2_2") (pintype "passive"))
      (node (ref "R7") (pin "2") (pinfunction "2_2") (pintype "passive"))
    )
    (net (code "32") (name "Net-(D1-K)") (class "Default")
      (node (ref "C12") (pin "2") (pinfunction "2_2") (pintype "passive"))
      (node (ref "D1") (pin "2") (pinfunction "K_2") (pintype "passive"))
      (node (ref "D2") (pin "2") (pinfunction "K_2") (pintype "passive"))
      (node (ref "D3") (pin "3") (pinfunction "A_3") (pintype "passive"))
      (node (ref "R11") (pin "2") (pinfunction "2_2") (pintype "passive"))
      (node (ref "U4") (pin "2") (pinfunction "IN+_2") (pintype "input"))
    )
    (net (code "33") (name "Net-(D2-A)") (class "Default")
      (node (ref "D2") (pin "1") (pinfunction "A_1") (pintype "passive"))
      (node (ref "R6") (pin "2") (pinfunction "2_2") (pintype "passive"))
      (node (ref "R8") (pin "2") (pinfunction "2_2") (pintype "passive"))
    )
    (net (code "34") (name "Net-(D4-A)") (class "Default")
      (node (ref "D3") (pin "2") (pintype "passive"))
      (node (ref "D4") (pin "3") (pinfunction "A_3") (pintype "passive"))
    )
    (net (code "35") (name "Net-(D5-A)") (class "Default")
      (node (ref "D4") (pin "2") (pintype "passive"))
      (node (ref "D5") (pin "3") (pinfunction "A_3") (pintype "passive"))
    )
    (net (code "36") (name "Net-(D6-K)") (class "Default")
      (node (ref "D6") (pin "2") (pinfunction "K_2") (pintype "passive"))
      (node (ref "D7") (pin "3") (pinfunction "A_3") (pintype "passive"))
    )
    (net (code "37") (name "Net-(D7-K)") (class "Default")
      (node (ref "D7") (pin "2") (pinfunction "K_2") (pintype "passive"))
      (node (ref "D8") (pin "3") (pinfunction "A_3") (pintype "passive"))
    )
    (net (code "38") (name "Net-(D10-A)") (class "Default")
      (node (ref "D10") (pin "3") (pinfunction "A_3") (pintype "passive"))
      (node (ref "D11") (pin "2") (pinfunction "K_2") (pintype "passive"))
    )
    (net (code "39") (name "Net-(D10-K)") (class "Default")
      (node (ref "D10") (pin "2") (pinfunction "K_2") (pintype "passive"))
      (node (ref "D9") (pin "3") (pinfunction "A_3") (pintype "passive"))
    )
    (net (code "40") (name "Net-(D12-K)") (class "Default")
      (node (ref "C21") (pin "2") (pinfunction "2_2") (pintype "passive"))
      (node (ref "D12") (pin "2") (pinfunction "K_2") (pintype "passive"))
      (node (ref "R15") (pin "2") (pinfunction "2_2") (pintype "passive"))
      (node (ref "TP5") (pin "1") (pinfunction "NC_1") (pintype "passive"))
      (node (ref "U6") (pin "2") (pinfunction "IN_2") (pintype "passive"))
      (node (ref "U8") (pin "2") (pinfunction "IN_2") (pintype "passive"))
    )
    (net (code "41") (name "Net-(D13-K)") (class "Default")
      (node (ref "C20") (pin "2") (pinfunction "2_2") (pintype "passive"))
      (node (ref "D13") (pin "2") (pinfunction "K_2") (pintype "passive"))
      (node (ref "R16") (pin "2") (pinfunction "2_2") (pintype "passive"))
      (node (ref "TP4") (pin "1") (pinfunction "NC_1") (pintype "passive"))
      (node (ref "U5") (pin "2") (pinfunction "IN_2") (pintype "passive"))
      (node (ref "U7") (pin "2") (pinfunction "IN_2") (pintype "passive"))
    )
    (net (code "42") (name "Net-(D14-A)") (class "Default")
      (node (ref "D14") (pin "3") (pinfunction "A_3") (pintype "passive"))
      (node (ref "R19") (pin "1") (pinfunction "1_1") (pintype "passive"))
      (node (ref "U5") (pin "6") (pinfunction "OUT1_6") (pintype "passive"))
      (node (ref "U5") (pin "7") (pinfunction "OUT2_7") (pintype "passive"))
    )
    (net (code "43") (name "Net-(D15-A)") (class "Default")
      (node (ref "D15") (pin "3") (pinfunction "A_3") (pintype "passive"))
      (node (ref "R20") (pin "1") (pinfunction "1_1") (pintype "passive"))
      (node (ref "U6") (pin "6") (pinfunction "OUT1_6") (pintype "passive"))
      (node (ref "U6") (pin "7") (pinfunction "OUT2_7") (pintype "passive"))
    )
    (net (code "44") (name "Net-(D16-A)") (class "Default")
      (node (ref "D16") (pin "3") (pinfunction "A_3") (pintype "passive"))
      (node (ref "R21") (pin "1") (pinfunction "1_1") (pintype "passive"))
      (node (ref "U7") (pin "6") (pinfunction "OUT1_6") (pintype "passive"))
      (node (ref "U7") (pin "7") (pinfunction "OUT2_7") (pintype "passive"))
    )
    (net (code "45") (name "Net-(D17-A)") (class "Default")
      (node (ref "D17") (pin "3") (pinfunction "A_3") (pintype "passive"))
      (node (ref "R22") (pin "1") (pinfunction "1_1") (pintype "passive"))
      (node (ref "U8") (pin "6") (pinfunction "OUT1_6") (pintype "passive"))
      (node (ref "U8") (pin "7") (pinfunction "OUT2_7") (pintype "passive"))
    )
    (net (code "46") (name "Net-(D18-A)") (class "Default")
      (node (ref "D18") (pin "1") (pinfunction "A_1") (pintype "passive"))
      (node (ref "D30") (pin "1") (pinfunction "K_1") (pintype "passive"))
      (node (ref "D32") (pin "2") (pinfunction "A_2") (pintype "passive"))
      (node (ref "R31") (pin "2") (pinfunction "2_2") (pintype "passive"))
      (node (ref "R35") (pin "1") (pinfunction "1_1") (pintype "passive"))
      (node (ref "TP11") (pin "1") (pinfunction "NC_1") (pintype "passive"))
      (node (ref "U10") (pin "3") (pinfunction "+IN_3") (pintype "input"))
      (node (ref "U11") (pin "3") (pinfunction "+IN_3") (pintype "input"))
    )
    (net (code "47") (name "Net-(D18-K)") (class "Default")
      (node (ref "C33") (pin "2") (pinfunction "2_2") (pintype "passive"))
      (node (ref "D18") (pin "2") (pinfunction "K_2") (pintype "passive"))
      (node (ref "D19") (pin "2") (pinfunction "K_2") (pintype "passive"))
      (node (ref "R24") (pin "1") (pinfunction "1_1") (pintype "passive"))
      (node (ref "U9") (pin "2") (pinfunction "IN+_2") (pintype "input"))
    )
    (net (code "48") (name "Net-(D19-A)") (class "Default")
      (node (ref "D19") (pin "1") (pinfunction "A_1") (pintype "passive"))
      (node (ref "D31") (pin "1") (pinfunction "K_1") (pintype "passive"))
      (node (ref "D33") (pin "2") (pinfunction "A_2") (pintype "passive"))
      (node (ref "R32") (pin "1") (pinfunction "1_1") (pintype "passive"))
      (node (ref "R34") (pin "2") (pinfunction "2_2") (pintype "passive"))
      (node (ref "TP10") (pin "1") (pinfunction "NC_1") (pintype "passive"))
      (node (ref "U12") (pin "3") (pinfunction "+IN_3") (pintype "input"))
      (node (ref "U13") (pin "3") (pinfunction "+IN_3") (pintype "input"))
    )
    (net (code "49") (name "Net-(D20-A)") (class "Default")
      (node (ref "D20") (pin "2") (pinfunction "A_2") (pintype "passive"))
      (node (ref "T2") (pin "4") (pinfunction "Sec1+_4") (pintype "passive"))
    )
    (net (code "50") (name "Net-(D20-K)") (class "Default")
      (node (ref "D20") (pin "1") (pinfunction "K_1") (pintype "passive"))
      (node (ref "D26") (pin "1") (pinfunction "K_1") (pintype "passive"))
      (node (ref "Q4") (pin "1") (pinfunction "G_1") (pintype "passive"))
      (node (ref "Q7") (pin "1") (pinfunction "G_1") (pintype "passive"))
      (node (ref "R28") (pin "1") (pinfunction "1_1") (pintype "passive"))
    )
    (net (code "51") (name "Net-(D21-A)") (class "Default")
      (node (ref "C35") (pin "1") (pinfunction "1_1") (pintype "passive"))
      (node (ref "D21") (pin "2") (pinfunction "A_2") (pintype "passive"))
      (node (ref "D27") (pin "1") (pinfunction "A_1") (pintype "passive"))
      (node (ref "Q1") (pin "2") (pinfunction "S_2") (pintype "passive"))
      (node (ref "Q5") (pin "3") (pinfunction "G_3") (pintype "passive"))
      (node (ref "R25") (pin "2") (pinfunction "2_2") (pintype "passive"))
      (node (ref "T1") (pin "1") (pinfunction "Sec+_1") (pintype "passive"))
    )
    (net (code "52") (name "Net-(D21-K)") (class "Default")
      (node (ref "D21") (pin "1") (pinfunction "K_1") (pintype "passive"))
      (node (ref "T2") (pin "3") (pinfunction "Sec2-_3") (pintype "passive"))
    )
    (net (code "53") (name "Net-(D22-A)") (class "Default")
      (node (ref "D22") (pin "2") (pinfunction "A_2") (pintype "passive"))
      (node (ref "T1") (pin "2") (pinfunction "Sec-_2") (pintype "passive"))
    )
    (net (code "54") (name "Net-(D22-K)") (class "Default")
      (node (ref "D22") (pin "1") (pinfunction "K_1") (pintype "passive"))
      (node (ref "D27") (pin "2") (pinfunction "K_2") (pintype "passive"))
      (node (ref "Q1") (pin "1") (pinfunction "G_1") (pintype "passive"))
      (node (ref "R25") (pin "1") (pinfunction "1_1") (pintype "passive"))
    )
    (net (code "55") (name "Net-(D23-A)") (class "Default")
      (node (ref "D23") (pin "2") (pinfunction "A_2") (pintype "passive"))
      (node (ref "T4") (pin "4") (pinfunction "Sec1+_4") (pintype "passive"))
    )
    (net (code "56") (name "Net-(D23-K)") (class "Default")
      (node (ref "D23") (pin "1") (pinfunction "K_1") (pintype "passive"))
      (node (ref "D28") (pin "1") (pinfunction "K_1") (pintype "passive"))
      (node (ref "Q3") (pin "1") (pinfunction "G_1") (pintype "passive"))
      (node (ref "Q8") (pin "1") (pinfunction "G_1") (pintype "passive"))
      (node (ref "R29") (pin "1") (pinfunction "1_1") (pintype "passive"))
    )
    (net (code "57") (name "Net-(D24-A)") (class "Default")
      (node (ref "C34") (pin "1") (pinfunction "1_1") (pintype "passive"))
      (node (ref "D24") (pin "2") (pinfunction "A_2") (pintype "passive"))
      (node (ref "D29") (pin "1") (pinfunction "A_1") (pintype "passive"))
      (node (ref "Q2") (pin "2") (pinfunction "S_2") (pintype "passive"))
      (node (ref "Q6") (pin "3") (pinfunction "G_3") (pintype "passive"))
      (node (ref "R26") (pin "2") (pinfunction "2_2") (pintype "passive"))
      (node (ref "T3") (pin "1") (pinfunction "Sec+_1") (pintype "passive"))
    )
    (net (code "58") (name "Net-(D24-K)") (class "Default")
      (node (ref "D24") (pin "1") (pinfunction "K_1") (pintype "passive"))
      (node (ref "T4") (pin "3") (pinfunction "Sec2-_3") (pintype "passive"))
    )
    (net (code "59") (name "Net-(D25-A)") (class "Default")
      (node (ref "D25") (pin "2") (pinfunction "A_2") (pintype "passive"))
      (node (ref "T3") (pin "2") (pinfunction "Sec-_2") (pintype "passive"))
    )
    (net (code "60") (name "Net-(D25-K)") (class "Default")
      (node (ref "D25") (pin "1") (pinfunction "K_1") (pintype "passive"))
      (node (ref "D29") (pin "2") (pinfunction "K_2") (pintype "passive"))
      (node (ref "Q2") (pin "1") (pinfunction "G_1") (pintype "passive"))
      (node (ref "R26") (pin "1") (pinfunction "1_1") (pintype "passive"))
    )
    (net (code "61") (name "Net-(D26-A)") (class "Default")
      (node (ref "C35") (pin "2") (pinfunction "2_2") (pintype "passive"))
      (node (ref "C37") (pin "1") (pinfunction "1_1") (pintype "passive"))
      (node (ref "D26") (pin "2") (pinfunction "A_2") (pintype "passive"))
      (node (ref "Q1") (pin "3") (pinfunction "D_3") (pintype "passive"))
      (node (ref "Q4") (pin "3") (pinfunction "S_3") (pintype "passive"))
      (node (ref "Q5") (pin "1") (pinfunction "D_1") (pintype "passive"))
      (node (ref "Q7") (pin "3") (pinfunction "S_3") (pintype "passive"))
      (node (ref "T2") (pin "2") (pinfunction "Sec2+_2") (pintype "passive"))
      (node (ref "T2") (pin "5") (pinfunction "Sec1-_5") (pintype "passive"))
      (node (ref "TP7") (pin "1") (pinfunction "NC_1") (pintype "passive"))
    )
    (net (code "62") (name "Net-(D28-A)") (class "Default")
      (node (ref "C34") (pin "2") (pinfunction "2_2") (pintype "passive"))
      (node (ref "C38") (pin "1") (pinfunction "1_1") (pintype "passive"))
      (node (ref "D28") (pin "2") (pinfunction "A_2") (pintype "passive"))
      (node (ref "Q2") (pin "3") (pinfunction "D_3") (pintype "passive"))
      (node (ref "Q3") (pin "3") (pinfunction "S_3") (pintype "passive"))
      (node (ref "Q6") (pin "1") (pinfunction "D_1") (pintype "passive"))
      (node (ref "Q8") (pin "3") (pinfunction "S_3") (pintype "passive"))
      (node (ref "T4") (pin "2") (pinfunction "Sec2+_2") (pintype "passive"))
      (node (ref "T4") (pin "5") (pinfunction "Sec1-_5") (pintype "passive"))
      (node (ref "TP8") (pin "1") (pinfunction "NC_1") (pintype "passive"))
    )
    (net (code "63") (name "Net-(D34-A)") (class "Default")
      (node (ref "D34") (pin "3") (pinfunction "A_3") (pintype "passive"))
      (node (ref "D36") (pin "2") (pinfunction "K_2") (pintype "passive"))
    )
    (net (code "64") (name "Net-(D34-K)") (class "Default")
      (node (ref "C88") (pin "1") (pinfunction "1_1") (pintype "passive"))
      (node (ref "C89") (pin "1") (pinfunction "1_1") (pintype "passive"))
      (node (ref "D34") (pin "2") (pinfunction "K_2") (pintype "passive"))
      (node (ref "U18") (pin "3") (pinfunction "V+_3") (pintype "power_in"))
    )
    (net (code "65") (name "Net-(D35-A)") (class "Default")
      (node (ref "C90") (pin "2") (pinfunction "2_2") (pintype "passive"))
      (node (ref "C91") (pin "1") (pinfunction "1_1") (pintype "passive"))
      (node (ref "D35") (pin "3") (pinfunction "A_3") (pintype "passive"))
      (node (ref "U18") (pin "6") (pinfunction "V-_6") (pintype "power_in"))
    )
    (net (code "66") (name "Net-(D35-K)") (class "Default")
      (node (ref "D35") (pin "2") (pinfunction "K_2") (pintype "passive"))
      (node (ref "D37") (pin "3") (pinfunction "A_3") (pintype "passive"))
    )
    (net (code "67") (name "Net-(Q5-S)") (class "Default")
      (node (ref "C37") (pin "2") (pinfunction "2_2") (pintype "passive"))
      (node (ref "Q5") (pin "2") (pinfunction "S_2") (pintype "passive"))
      (node (ref "R28") (pin "2") (pinfunction "2_2") (pintype "passive"))
    )
    (net (code "68") (name "Net-(Q6-S)") (class "Default")
      (node (ref "C38") (pin "2") (pinfunction "2_2") (pintype "passive"))
      (node (ref "Q6") (pin "2") (pinfunction "S_2") (pintype "passive"))
      (node (ref "R29") (pin "2") (pinfunction "2_2") (pintype "passive"))
    )
    (net (code "69") (name "Net-(Q7-D)") (class "Default")
      (node (ref "Q7") (pin "2") (pinfunction "D_2") (pintype "passive"))
      (node (ref "R31") (pin "1") (pinfunction "1_1") (pintype "passive"))
    )
    (net (code "70") (name "Net-(Q8-D)") (class "Default")
      (node (ref "Q8") (pin "2") (pinfunction "D_2") (pintype "passive"))
      (node (ref "R32") (pin "2") (pinfunction "2_2") (pintype "passive"))
    )
    (net (code "71") (name "Net-(Q9A-D-Pad5)") (class "Default")
      (node (ref "Q9") (pin "5") (pinfunction "D_5") (pintype "passive"))
      (node (ref "Q9") (pin "6") (pinfunction "D_6") (pintype "passive"))
      (node (ref "R34") (pin "1") (pinfunction "1_1") (pintype "passive"))
    )
    (net (code "72") (name "Net-(Q9A-G)") (class "Default")
      (node (ref "Q9") (pin "2") (pinfunction "G_2") (pintype "passive"))
      (node (ref "Q9") (pin "4") (pinfunction "G_4") (pintype "passive"))
      (node (ref "R30") (pin "2") (pinfunction "2_2") (pintype "passive"))
      (node (ref "R33") (pin "2") (pinfunction "2_2") (pintype "passive"))
      (node (ref "TP9") (pin "1") (pinfunction "NC_1") (pintype "passive"))
    )
    (net (code "73") (name "Net-(Q9A-S)") (class "Default")
      (node (ref "Q9") (pin "1") (pinfunction "S_1") (pintype "passive"))
      (node (ref "Q9") (pin "3") (pinfunction "S_3") (pintype "passive"))
      (node (ref "R36") (pin "1") (pinfunction "1_1") (pintype "passive"))
    )
    (net (code "74") (name "Net-(Q9B-D-Pad7)") (class "Default")
      (node (ref "Q9") (pin "7") (pinfunction "D_7") (pintype "passive"))
      (node (ref "Q9") (pin "8") (pinfunction "D_8") (pintype "passive"))
      (node (ref "R35") (pin "2") (pinfunction "2_2") (pintype "passive"))
    )
    (net (code "75") (name "Net-(R20-Pad2)") (class "Default")
      (node (ref "R20") (pin "2") (pinfunction "2_2") (pintype "passive"))
      (node (ref "T1") (pin "3") (pinfunction "Pri-_3") (pintype "passive"))
    )
    (net (code "76") (name "Net-(R22-Pad2)") (class "Default")
      (node (ref "R22") (pin "2") (pinfunction "2_2") (pintype "passive"))
      (node (ref "T3") (pin "3") (pinfunction "Pri-_3") (pintype "passive"))
    )
    (net (code "77") (name "Net-(R55-Pad2)") (class "Default")
      (node (ref "R55") (pin "2") (pinfunction "2_2") (pintype "passive"))
      (node (ref "R56") (pin "2") (pinfunction "2_2") (pintype "passive"))
      (node (ref "R67") (pin "1") (pinfunction "1_1") (pintype "passive"))
    )
    (net (code "78") (name "Net-(T2-Pri-)") (class "Default")
      (node (ref "R19") (pin "2") (pinfunction "2_2") (pintype "passive"))
      (node (ref "T2") (pin "1") (pinfunction "Pri-_1") (pintype "passive"))
    )
    (net (code "79") (name "Net-(T4-Pri-)") (class "Default")
      (node (ref "R21") (pin "2") (pinfunction "2_2") (pintype "passive"))
      (node (ref "T4") (pin "1") (pinfunction "Pri-_1") (pintype "passive"))
    )
    (net (code "80") (name "Net-(TP1-NC)") (class "Default")
      (node (ref "TP1") (pin "1") (pinfunction "NC_1") (pintype "passive"))
      (node (ref "U1") (pin "3") (pinfunction "OUTA_3") (pintype "passive"))
      (node (ref "U2") (pin "9") (pinfunction "B_9") (pintype "input"))
    )
    (net (code "81") (name "Net-(TP2-NC)") (class "Default")
      (node (ref "R27") (pin "1") (pinfunction "1_1") (pintype "passive"))
      (node (ref "TP2") (pin "1") (pinfunction "NC_1") (pintype "passive"))
      (node (ref "U1") (pin "5") (pinfunction "OUTC_5") (pintype "passive"))
    )
    (net (code "82") (name "Net-(TP12-NC)") (class "Default")
      (node (ref "C52") (pin "1") (pinfunction "1_1") (pintype "passive"))
      (node (ref "C63") (pin "1") (pinfunction "1_1") (pintype "passive"))
      (node (ref "R41") (pin "1") (pinfunction "1_1") (pintype "passive"))
      (node (ref "TP12") (pin "1") (pinfunction "NC_1") (pintype "passive"))
      (node (ref "U10") (pin "6") (pinfunction "OUTPUT_6") (pintype "output"))
      (node (ref "U14") (pin "1") (pinfunction "+IN_1") (pintype "input"))
    )
    (net (code "83") (name "Net-(TP13-NC)") (class "Default")
      (node (ref "C53") (pin "1") (pinfunction "1_1") (pintype "passive"))
      (node (ref "C64") (pin "1") (pinfunction "1_1") (pintype "passive"))
      (node (ref "R42") (pin "1") (pinfunction "1_1") (pintype "passive"))
      (node (ref "TP13") (pin "1") (pinfunction "NC_1") (pintype "passive"))
      (node (ref "U11") (pin "6") (pinfunction "OUTPUT_6") (pintype "output"))
      (node (ref "U15") (pin "1") (pinfunction "+IN_1") (pintype "input"))
    )
    (net (code "84") (name "Net-(TP14-NC)") (class "Default")
      (node (ref "C50") (pin "2") (pinfunction "2_2") (pintype "passive"))
      (node (ref "C62") (pin "1") (pinfunction "1_1") (pintype "passive"))
      (node (ref "R40") (pin "2") (pinfunction "2_2") (pintype "passive"))
      (node (ref "TP14") (pin "1") (pinfunction "NC_1") (pintype "passive"))
      (node (ref "U13") (pin "6") (pinfunction "OUTPUT_6") (pintype "output"))
      (node (ref "U15") (pin "8") (pinfunction "-IN_8") (pintype "input"))
    )
    (net (code "85") (name "Net-(TP15-NC)") (class "Default")
      (node (ref "C49") (pin "2") (pinfunction "2_2") (pintype "passive"))
      (node (ref "C61") (pin "1") (pinfunction "1_1") (pintype "passive"))
      (node (ref "R39") (pin "2") (pinfunction "2_2") (pintype "passive"))
      (node (ref "TP15") (pin "1") (pinfunction "NC_1") (pintype "passive"))
      (node (ref "U12") (pin "6") (pinfunction "OUTPUT_6") (pintype "output"))
      (node (ref "U14") (pin "8") (pinfunction "-IN_8") (pintype "input"))
    )
    (net (code "86") (name "Net-(TP16-NC)") (class "Default")
      (node (ref "C73") (pin "2") (pinfunction "2_2") (pintype "passive"))
      (node (ref "R53") (pin "2") (pinfunction "2_2") (pintype "passive"))
      (node (ref "TP16") (pin "1") (pinfunction "NC_1") (pintype "passive"))
      (node (ref "U14") (pin "6") (pinfunction "OUTPUT_6") (pintype "output"))
    )
    (net (code "87") (name "Net-(TP18-NC)") (class "Default")
      (node (ref "TP18") (pin "1") (pinfunction "NC_1") (pintype "passive"))
      (node (ref "U17") (pin "8") (pinfunction "VO_8") (pintype "passive"))
      (node (ref "U18") (pin "8") (pinfunction "Din+_8") (pintype "input"))
    )
    (net (code "88") (name "Net-(TP19-NC)") (class "Default")
      (node (ref "C81") (pin "1") (pinfunction "1_1") (pintype "passive"))
      (node (ref "C83") (pin "1") (pinfunction "1_1") (pintype "passive"))
      (node (ref "C85") (pin "2") (pinfunction "2_2") (pintype "passive"))
      (node (ref "R58") (pin "2") (pinfunction "2_2") (pintype "passive"))
      (node (ref "TP19") (pin "1") (pinfunction "NC_1") (pintype "passive"))
      (node (ref "U16") (pin "6") (pinfunction "OUTPUT_6") (pintype "output"))
    )
    (net (code "89") (name "Net-(TP23-NC)") (class "Default")
      (node (ref "C74") (pin "2") (pinfunction "2_2") (pintype "passive"))
      (node (ref "R54") (pin "2") (pinfunction "2_2") (pintype "passive"))
      (node (ref "TP23") (pin "1") (pinfunction "NC_1") (pintype "passive"))
      (node (ref "U15") (pin "6") (pinfunction "OUTPUT_6") (pintype "output"))
    )
    (net (code "90") (name "Net-(U1-INA+)") (class "Default")
      (node (ref "R1") (pin "2") (pinfunction "2_2") (pintype "passive"))
      (node (ref "U1") (pin "2") (pinfunction "INA+_2") (pintype "passive"))
    )
    (net (code "91") (name "Net-(U1-INA-)") (class "Default")
      (node (ref "R2") (pin "2") (pinfunction "2_2") (pintype "passive"))
      (node (ref "U1") (pin "1") (pinfunction "INA-_1") (pintype "passive"))
    )
    (net (code "92") (name "Net-(U1-INC+)") (class "Default")
      (node (ref "R3") (pin "2") (pinfunction "2_2") (pintype "passive"))
      (node (ref "U1") (pin "6") (pinfunction "INC+_6") (pintype "passive"))
    )
    (net (code "93") (name "Net-(U1-INC-)") (class "Default")
      (node (ref "R4") (pin "2") (pinfunction "2_2") (pintype "passive"))
      (node (ref "U1") (pin "7") (pinfunction "INC-_7") (pintype "passive"))
    )
    (net (code "94") (name "Net-(U2A-A)") (class "Default")
      (node (ref "C16") (pin "1") (pinfunction "1_1") (pintype "passive"))
      (node (ref "R14") (pin "2") (pinfunction "2_2") (pintype "passive"))
      (node (ref "U2") (pin "1") (pinfunction "A_1") (pintype "input"))
    )
    (net (code "95") (name "Net-(U2A-~{O})") (class "Default")
      (node (ref "U2") (pin "13") (pinfunction "A_13") (pintype "input"))
      (node (ref "U2") (pin "3") (pinfunction "~{O}_3") (pintype "output"))
    )
    (net (code "96") (name "Net-(U2C-B)") (class "Default")
      (node (ref "U2") (pin "12") (pinfunction "B_12") (pintype "input"))
      (node (ref "U3") (pin "10") (pinfunction "~{O}_10") (pintype "output"))
    )
    (net (code "97") (name "Net-(U2C-~{O})") (class "Default")
      (node (ref "C21") (pin "1") (pinfunction "1_1") (pintype "passive"))
      (node (ref "U2") (pin "11") (pinfunction "~{O}_11") (pintype "output"))
    )
    (net (code "98") (name "Net-(U2D-~{O})") (class "Default")
      (node (ref "R9") (pin "2") (pinfunction "2_2") (pintype "passive"))
      (node (ref "U2") (pin "8") (pinfunction "~{O}_8") (pintype "output"))
      (node (ref "U3") (pin "11") (pinfunction "A_11") (pintype "input"))
    )
    (net (code "99") (name "Net-(U3C-A)") (class "Default")
      (node (ref "U3") (pin "5") (pinfunction "A_5") (pintype "input"))
      (node (ref "U4") (pin "7") (pinfunction "OUT_7") (pintype "output"))
    )
    (net (code "100") (name "Net-(U3F-A)") (class "Default")
      (node (ref "C13") (pin "1") (pinfunction "1_1") (pintype "passive"))
      (node (ref "R9") (pin "1") (pinfunction "1_1") (pintype "passive"))
      (node (ref "U3") (pin "9") (pinfunction "A_9") (pintype "input"))
    )
    (net (code "101") (name "Net-(U3F-~{O})") (class "Default")
      (node (ref "C20") (pin "1") (pinfunction "1_1") (pintype "passive"))
      (node (ref "R14") (pin "1") (pinfunction "1_1") (pintype "passive"))
      (node (ref "U3") (pin "8") (pinfunction "~{O}_8") (pintype "output"))
    )
    (net (code "102") (name "Net-(U4-IN-)") (class "Default")
      (node (ref "C15") (pin "2") (pinfunction "2_2") (pintype "passive"))
      (node (ref "R10") (pin "1") (pinfunction "1_1") (pintype "passive"))
      (node (ref "R12") (pin "1") (pinfunction "1_1") (pintype "passive"))
      (node (ref "U4") (pin "3") (pinfunction "IN-_3") (pintype "input"))
    )
    (net (code "103") (name "Net-(U4-~{latch})") (class "Default")
      (node (ref "R13") (pin "1") (pinfunction "1_1") (pintype "passive"))
      (node (ref "U4") (pin "5") (pinfunction "~{latch}_5") (pintype "passive"))
    )
    (net (code "104") (name "Net-(U9-IN-)") (class "Default")
      (node (ref "C32") (pin "2") (pinfunction "2_2") (pintype "passive"))
      (node (ref "R18") (pin "1") (pinfunction "1_1") (pintype "passive"))
      (node (ref "R23") (pin "1") (pinfunction "1_1") (pintype "passive"))
      (node (ref "U9") (pin "3") (pinfunction "IN-_3") (pintype "input"))
    )
    (net (code "105") (name "Net-(U9-~{latch})") (class "Default")
      (node (ref "R17") (pin "1") (pinfunction "1_1") (pintype "passive"))
      (node (ref "U9") (pin "5") (pinfunction "~{latch}_5") (pintype "passive"))
    )
    (net (code "106") (name "Net-(U10--IN)") (class "Default")
      (node (ref "C39") (pin "2") (pinfunction "2_2") (pintype "passive"))
      (node (ref "C52") (pin "2") (pinfunction "2_2") (pintype "passive"))
      (node (ref "R41") (pin "2") (pinfunction "2_2") (pintype "passive"))
      (node (ref "U10") (pin "2") (pinfunction "-IN_2") (pintype "input"))
    )
    (net (code "107") (name "Net-(U10--VS)") (class "Default")
      (node (ref "C46") (pin "2") (pinfunction "2_2") (pintype "passive"))
      (node (ref "C47") (pin "2") (pinfunction "2_2") (pintype "passive"))
      (node (ref "R45") (pin "1") (pinfunction "1_1") (pintype "passive"))
      (node (ref "U10") (pin "4") (pinfunction "-VS_4") (pintype "power_in"))
    )
    (net (code "108") (name "Net-(U10-NEU)") (class "Default")
      (node (ref "C63") (pin "2") (pinfunction "2_2") (pintype "passive"))
      (node (ref "U10") (pin "8") (pinfunction "NEU_8") (pintype "power_in"))
    )
    (net (code "109") (name "Net-(U11--IN)") (class "Default")
      (node (ref "C40") (pin "2") (pinfunction "2_2") (pintype "passive"))
      (node (ref "C53") (pin "2") (pinfunction "2_2") (pintype "passive"))
      (node (ref "R42") (pin "2") (pinfunction "2_2") (pintype "passive"))
      (node (ref "U11") (pin "2") (pinfunction "-IN_2") (pintype "input"))
    )
    (net (code "110") (name "Net-(U11--VS)") (class "Default")
      (node (ref "C43") (pin "2") (pinfunction "2_2") (pintype "passive"))
      (node (ref "C48") (pin "2") (pinfunction "2_2") (pintype "passive"))
      (node (ref "R47") (pin "1") (pinfunction "1_1") (pintype "passive"))
      (node (ref "U11") (pin "4") (pinfunction "-VS_4") (pintype "power_in"))
    )
    (net (code "111") (name "Net-(U11-NEU)") (class "Default")
      (node (ref "C64") (pin "2") (pinfunction "2_2") (pintype "passive"))
      (node (ref "U11") (pin "8") (pinfunction "NEU_8") (pintype "power_in"))
    )
    (net (code "112") (name "Net-(U12--IN)") (class "Default")
      (node (ref "C49") (pin "1") (pinfunction "1_1") (pintype "passive"))
      (node (ref "R37") (pin "2") (pinfunction "2_2") (pintype "passive"))
      (node (ref "R39") (pin "1") (pinfunction "1_1") (pintype "passive"))
      (node (ref "U12") (pin "2") (pinfunction "-IN_2") (pintype "input"))
    )
    (net (code "113") (name "Net-(U12--VS)") (class "Default")
      (node (ref "C41") (pin "2") (pinfunction "2_2") (pintype "passive"))
      (node (ref "C42") (pin "2") (pinfunction "2_2") (pintype "passive"))
      (node (ref "R46") (pin "1") (pinfunction "1_1") (pintype "passive"))
      (node (ref "U12") (pin "4") (pinfunction "-VS_4") (pintype "power_in"))
    )
    (net (code "114") (name "Net-(U12-NEU)") (class "Default")
      (node (ref "C61") (pin "2") (pinfunction "2_2") (pintype "passive"))
      (node (ref "U12") (pin "8") (pinfunction "NEU_8") (pintype "power_in"))
    )
    (net (code "115") (name "Net-(U13--IN)") (class "Default")
      (node (ref "C50") (pin "1") (pinfunction "1_1") (pintype "passive"))
      (node (ref "R38") (pin "2") (pinfunction "2_2") (pintype "passive"))
      (node (ref "R40") (pin "1") (pinfunction "1_1") (pintype "passive"))
      (node (ref "U13") (pin "2") (pinfunction "-IN_2") (pintype "input"))
    )
    (net (code "116") (name "Net-(U13--VS)") (class "Default")
      (node (ref "C44") (pin "2") (pinfunction "2_2") (pintype "passive"))
      (node (ref "C45") (pin "1") (pinfunction "1_1") (pintype "passive"))
      (node (ref "R48") (pin "1") (pinfunction "1_1") (pintype "passive"))
      (node (ref "U13") (pin "4") (pinfunction "-VS_4") (pintype "power_in"))
    )
    (net (code "117") (name "Net-(U13-NEU)") (class "Default")
      (node (ref "C62") (pin "2") (pinfunction "2_2") (pintype "passive"))
      (node (ref "U13") (pin "8") (pinfunction "NEU_8") (pintype "power_in"))
    )
    (net (code "118") (name "Net-(U14-FB)") (class "Default")
      (node (ref "R51") (pin "1") (pinfunction "1_1") (pintype "passive"))
      (node (ref "R53") (pin "1") (pinfunction "1_1") (pintype "passive"))
      (node (ref "U14") (pin "5") (pinfunction "FB_5") (pintype "power_in"))
    )
    (net (code "119") (name "Net-(U15-FB)") (class "Default")
      (node (ref "R52") (pin "1") (pinfunction "1_1") (pintype "passive"))
      (node (ref "R54") (pin "1") (pinfunction "1_1") (pintype "passive"))
      (node (ref "U15") (pin "5") (pinfunction "FB_5") (pintype "power_in"))
    )
    (net (code "120") (name "Net-(U16-+IN)") (class "Default")
      (node (ref "R69") (pin "1") (pinfunction "1_1") (pintype "passive"))
      (node (ref "U16") (pin "3") (pinfunction "+IN_3") (pintype "input"))
    )
    (net (code "121") (name "Net-(U16--IN)") (class "Default")
      (node (ref "C81") (pin "2") (pinfunction "2_2") (pintype "passive"))
      (node (ref "R58") (pin "1") (pinfunction "1_1") (pintype "passive"))
      (node (ref "R67") (pin "2") (pinfunction "2_2") (pintype "passive"))
      (node (ref "U16") (pin "2") (pinfunction "-IN_2") (pintype "input"))
    )
    (net (code "122") (name "Net-(U16--VS)") (class "Default")
      (node (ref "C77") (pin "2") (pinfunction "2_2") (pintype "passive"))
      (node (ref "C78") (pin "2") (pinfunction "2_2") (pintype "passive"))
      (node (ref "R57") (pin "1") (pinfunction "1_1") (pintype "passive"))
      (node (ref "U16") (pin "4") (pinfunction "-VS_4") (pintype "power_in"))
    )
    (net (code "123") (name "Net-(U16-NEU)") (class "Default")
      (node (ref "C83") (pin "2") (pinfunction "2_2") (pintype "passive"))
      (node (ref "U16") (pin "8") (pinfunction "NEU_8") (pintype "power_in"))
    )
    (net (code "124") (name "Net-(U18-OUT+)") (class "Default")
      (node (ref "R63") (pin "1") (pinfunction "1_1") (pintype "passive"))
      (node (ref "U18") (pin "4") (pinfunction "OUT+_4") (pintype "passive"))
    )
    (net (code "125") (name "Net-(U18-OUT-)") (class "Default")
      (node (ref "R64") (pin "1") (pinfunction "1_1") (pintype "passive"))
      (node (ref "U18") (pin "5") (pinfunction "OUT-_5") (pintype "passive"))
    )
    (net (code "126") (name "Net-(U19-+IN)") (class "Default")
      (node (ref "C97") (pin "2") (pinfunction "2_2") (pintype "passive"))
      (node (ref "R71") (pin "2") (pinfunction "2_2") (pintype "passive"))
      (node (ref "U19") (pin "3") (pinfunction "+IN_3") (pintype "input"))
    )
    (net (code "127") (name "Net-(U19--IN)") (class "Default")
      (node (ref "R62") (pin "1") (pinfunction "1_1") (pintype "passive"))
      (node (ref "U19") (pin "2") (pinfunction "-IN_2") (pintype "input"))
    )
    (net (code "128") (name "Net-(U19--VS)") (class "Default")
      (node (ref "C86") (pin "2") (pinfunction "2_2") (pintype "passive"))
      (node (ref "C87") (pin "2") (pinfunction "2_2") (pintype "passive"))
      (node (ref "R61") (pin "1") (pinfunction "1_1") (pintype "passive"))
      (node (ref "U19") (pin "4") (pinfunction "-VS_4") (pintype "power_in"))
    )
    (net (code "129") (name "Net-(U19-NEU)") (class "Default")
      (node (ref "C94") (pin "2") (pinfunction "2_2") (pintype "passive"))
      (node (ref "U19") (pin "8") (pinfunction "NEU_8") (pintype "power_in"))
    )
    (net (code "130") (name "unconnected-(D3-Pad1)") (class "Default")
      (node (ref "D3") (pin "1") (pintype "passive+no_connect"))
    )
    (net (code "131") (name "unconnected-(D4-Pad1)") (class "Default")
      (node (ref "D4") (pin "1") (pintype "passive+no_connect"))
    )
    (net (code "132") (name "unconnected-(D5-Pad1)") (class "Default")
      (node (ref "D5") (pin "1") (pintype "passive+no_connect"))
    )
    (net (code "133") (name "unconnected-(D6-NC-Pad1)") (class "Default")
      (node (ref "D6") (pin "1") (pinfunction "NC_1") (pintype "passive+no_connect"))
    )
    (net (code "134") (name "unconnected-(D7-NC-Pad1)") (class "Default")
      (node (ref "D7") (pin "1") (pinfunction "NC_1") (pintype "passive+no_connect"))
    )
    (net (code "135") (name "unconnected-(D8-NC-Pad1)") (class "Default")
      (node (ref "D8") (pin "1") (pinfunction "NC_1") (pintype "passive+no_connect"))
    )
    (net (code "136") (name "unconnected-(D9-NC-Pad1)") (class "Default")
      (node (ref "D9") (pin "1") (pinfunction "NC_1") (pintype "passive+no_connect"))
    )
    (net (code "137") (name "unconnected-(D10-NC-Pad1)") (class "Default")
      (node (ref "D10") (pin "1") (pinfunction "NC_1") (pintype "passive+no_connect"))
    )
    (net (code "138") (name "unconnected-(D11-NC-Pad1)") (class "Default")
      (node (ref "D11") (pin "1") (pinfunction "NC_1") (pintype "passive+no_connect"))
    )
    (net (code "139") (name "unconnected-(D14-Pad1)") (class "Default")
      (node (ref "D14") (pin "1") (pintype "passive+no_connect"))
    )
    (net (code "140") (name "unconnected-(D15-Pad1)") (class "Default")
      (node (ref "D15") (pin "1") (pintype "passive+no_connect"))
    )
    (net (code "141") (name "unconnected-(D16-Pad1)") (class "Default")
      (node (ref "D16") (pin "1") (pintype "passive+no_connect"))
    )
    (net (code "142") (name "unconnected-(D17-Pad1)") (class "Default")
      (node (ref "D17") (pin "1") (pintype "passive+no_connect"))
    )
    (net (code "143") (name "unconnected-(D34-NC-Pad1)") (class "Default")
      (node (ref "D34") (pin "1") (pinfunction "NC_1") (pintype "passive"))
    )
    (net (code "144") (name "unconnected-(D35-NC-Pad1)") (class "Default")
      (node (ref "D35") (pin "1") (pinfunction "NC_1") (pintype "passive"))
    )
    (net (code "145") (name "unconnected-(D36-NC-Pad1)") (class "Default")
      (node (ref "D36") (pin "1") (pinfunction "NC_1") (pintype "passive"))
    )
    (net (code "146") (name "unconnected-(D37-NC-Pad1)") (class "Default")
      (node (ref "D37") (pin "1") (pinfunction "NC_1") (pintype "passive"))
    )
    (net (code "147") (name "unconnected-(U1-INB+-Pad14)") (class "Default")
      (node (ref "U1") (pin "14") (pinfunction "INB+_14") (pintype "passive+no_connect"))
    )
    (net (code "148") (name "unconnected-(U1-INB--Pad15)") (class "Default")
      (node (ref "U1") (pin "15") (pinfunction "INB-_15") (pintype "passive+no_connect"))
    )
    (net (code "149") (name "unconnected-(U1-IND+-Pad10)") (class "Default")
      (node (ref "U1") (pin "10") (pinfunction "IND+_10") (pintype "passive+no_connect"))
    )
    (net (code "150") (name "unconnected-(U1-IND--Pad9)") (class "Default")
      (node (ref "U1") (pin "9") (pinfunction "IND-_9") (pintype "passive+no_connect"))
    )
    (net (code "151") (name "unconnected-(U1-OUB-Pad13)") (class "Default")
      (node (ref "U1") (pin "13") (pinfunction "OUB_13") (pintype "passive+no_connect"))
    )
    (net (code "152") (name "unconnected-(U1-OUTD-Pad11)") (class "Default")
      (node (ref "U1") (pin "11") (pinfunction "OUTD_11") (pintype "passive+no_connect"))
    )
    (net (code "153") (name "unconnected-(U2B-~{O}-Pad6)") (class "Default")
      (node (ref "U2") (pin "6") (pinfunction "~{O}_6") (pintype "output+no_connect"))
    )
    (net (code "154") (name "unconnected-(U3A-~{O}-Pad2)") (class "Default")
      (node (ref "U3") (pin "2") (pinfunction "~{O}_2") (pintype "output+no_connect"))
    )
    (net (code "155") (name "unconnected-(U3B-~{O}-Pad4)") (class "Default")
      (node (ref "U3") (pin "4") (pinfunction "~{O}_4") (pintype "output+no_connect"))
    )
    (net (code "156") (name "unconnected-(U3D-~{O}-Pad12)") (class "Default")
      (node (ref "U3") (pin "12") (pinfunction "~{O}_12") (pintype "output+no_connect"))
    )
    (net (code "157") (name "unconnected-(U5-NC-Pad3)") (class "Default")
      (node (ref "U5") (pin "3") (pinfunction "NC_3") (pintype "passive+no_connect"))
    )
    (net (code "158") (name "unconnected-(U6-NC-Pad3)") (class "Default")
      (node (ref "U6") (pin "3") (pinfunction "NC_3") (pintype "passive+no_connect"))
    )
    (net (code "159") (name "unconnected-(U7-NC-Pad3)") (class "Default")
      (node (ref "U7") (pin "3") (pinfunction "NC_3") (pintype "passive+no_connect"))
    )
    (net (code "160") (name "unconnected-(U8-NC-Pad3)") (class "Default")
      (node (ref "U8") (pin "3") (pinfunction "NC_3") (pintype "passive+no_connect"))
    )
    (net (code "161") (name "unconnected-(U10-NC-Pad5)") (class "Default")
      (node (ref "U10") (pin "5") (pinfunction "NC_5") (pintype "power_in+no_connect"))
    )
    (net (code "162") (name "unconnected-(U10-Pad1)") (class "Default")
      (node (ref "U10") (pin "1") (pinfunction "1_1") (pintype "power_in+no_connect"))
    )
    (net (code "163") (name "unconnected-(U11-NC-Pad5)") (class "Default")
      (node (ref "U11") (pin "5") (pinfunction "NC_5") (pintype "power_in+no_connect"))
    )
    (net (code "164") (name "unconnected-(U11-Pad1)") (class "Default")
      (node (ref "U11") (pin "1") (pinfunction "1_1") (pintype "power_in+no_connect"))
    )
    (net (code "165") (name "unconnected-(U12-NC-Pad5)") (class "Default")
      (node (ref "U12") (pin "5") (pinfunction "NC_5") (pintype "power_in+no_connect"))
    )
    (net (code "166") (name "unconnected-(U12-Pad1)") (class "Default")
      (node (ref "U12") (pin "1") (pinfunction "1_1") (pintype "power_in+no_connect"))
    )
    (net (code "167") (name "unconnected-(U13-NC-Pad5)") (class "Default")
      (node (ref "U13") (pin "5") (pinfunction "NC_5") (pintype "power_in+no_connect"))
    )
    (net (code "168") (name "unconnected-(U13-Pad1)") (class "Default")
      (node (ref "U13") (pin "1") (pinfunction "1_1") (pintype "power_in+no_connect"))
    )
    (net (code "169") (name "unconnected-(U16-NC-Pad5)") (class "Default")
      (node (ref "U16") (pin "5") (pinfunction "NC_5") (pintype "power_in+no_connect"))
    )
    (net (code "170") (name "unconnected-(U16-Pad1)") (class "Default")
      (node (ref "U16") (pin "1") (pinfunction "1_1") (pintype "power_in+no_connect"))
    )
    (net (code "171") (name "unconnected-(U18-NC-Pad7)") (class "Default")
      (node (ref "U18") (pin "7") (pinfunction "NC_7") (pintype "passive+no_connect"))
    )
    (net (code "172") (name "unconnected-(U19-NC-Pad5)") (class "Default")
      (node (ref "U19") (pin "5") (pinfunction "NC_5") (pintype "power_in+no_connect"))
    )
    (net (code "173") (name "unconnected-(U19-Pad1)") (class "Default")
      (node (ref "U19") (pin "1") (pinfunction "1_1") (pintype "power_in+no_connect"))
    )
  )
)
